# core_io2.net
KiCad netlist of a schematic drawn in EAGLE
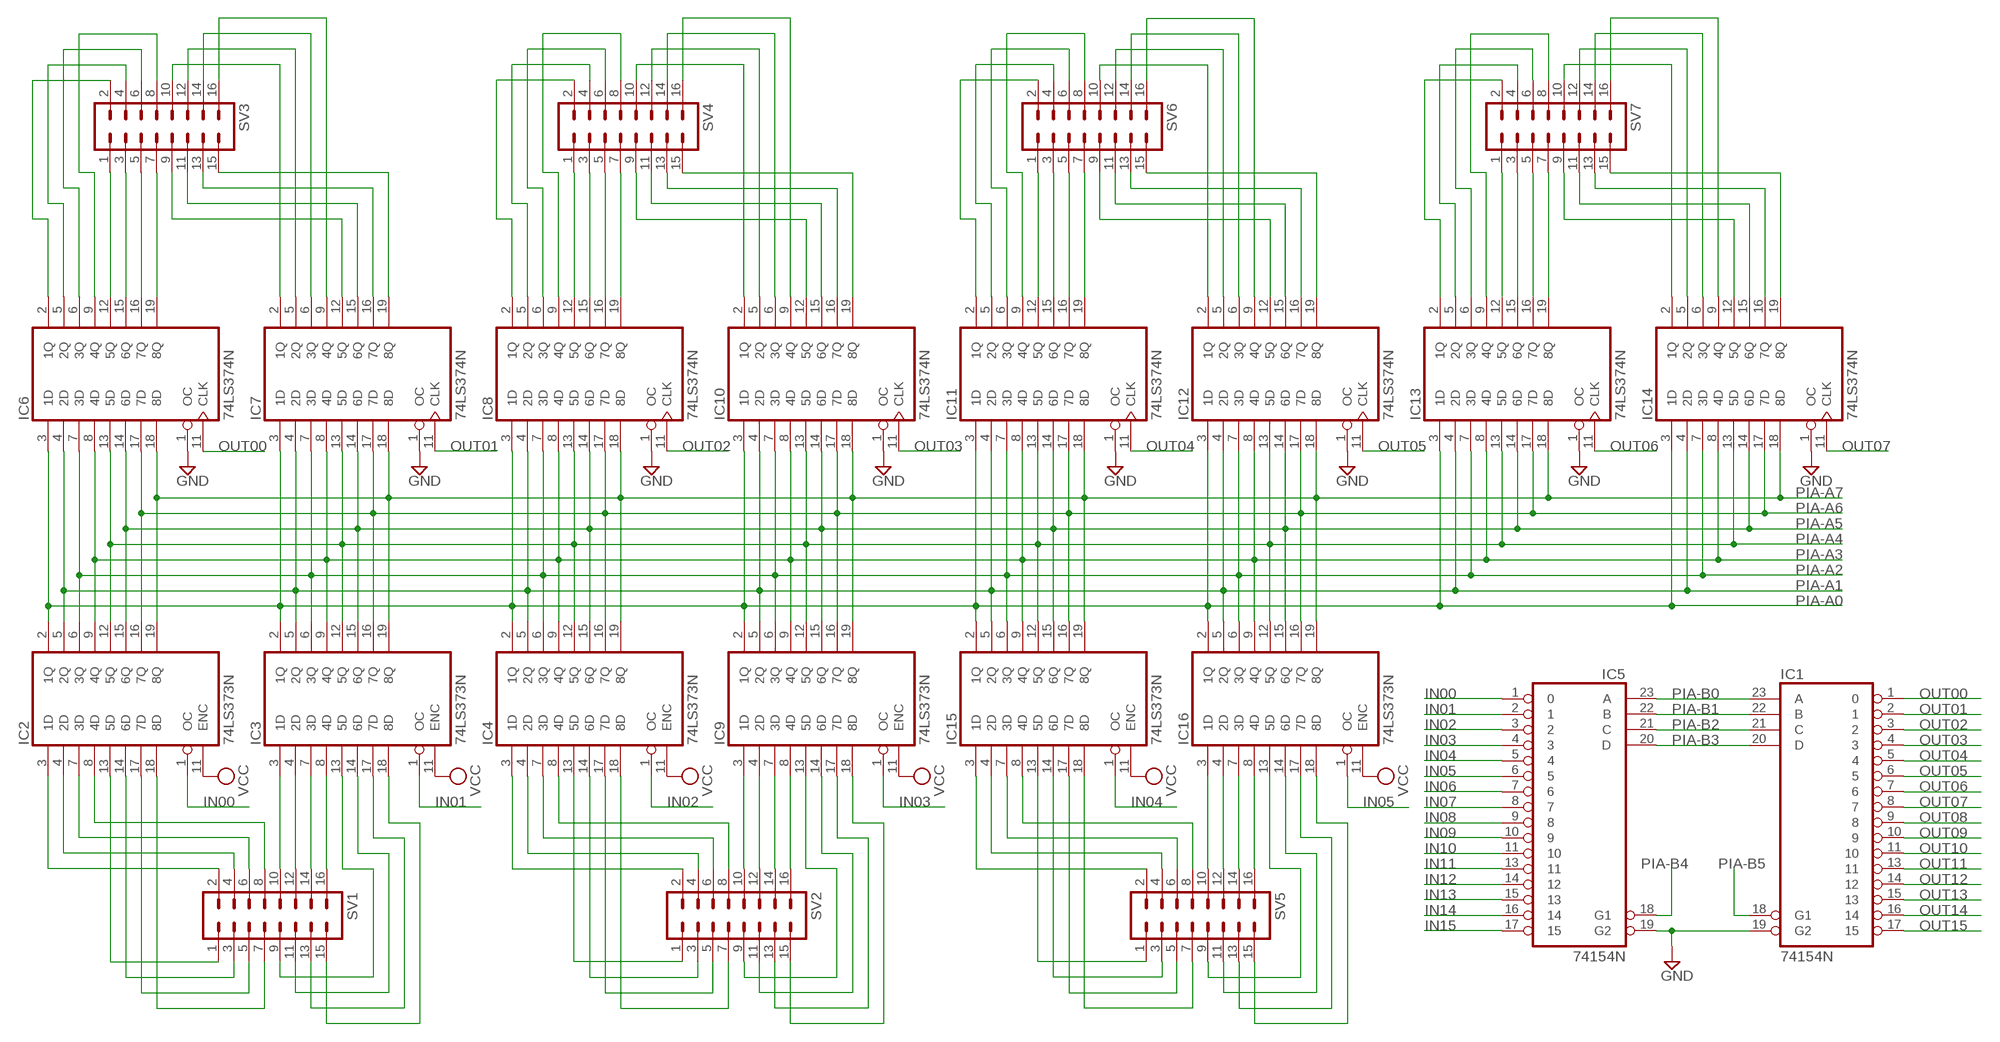
[diagram p0: schematic, sheet 1]
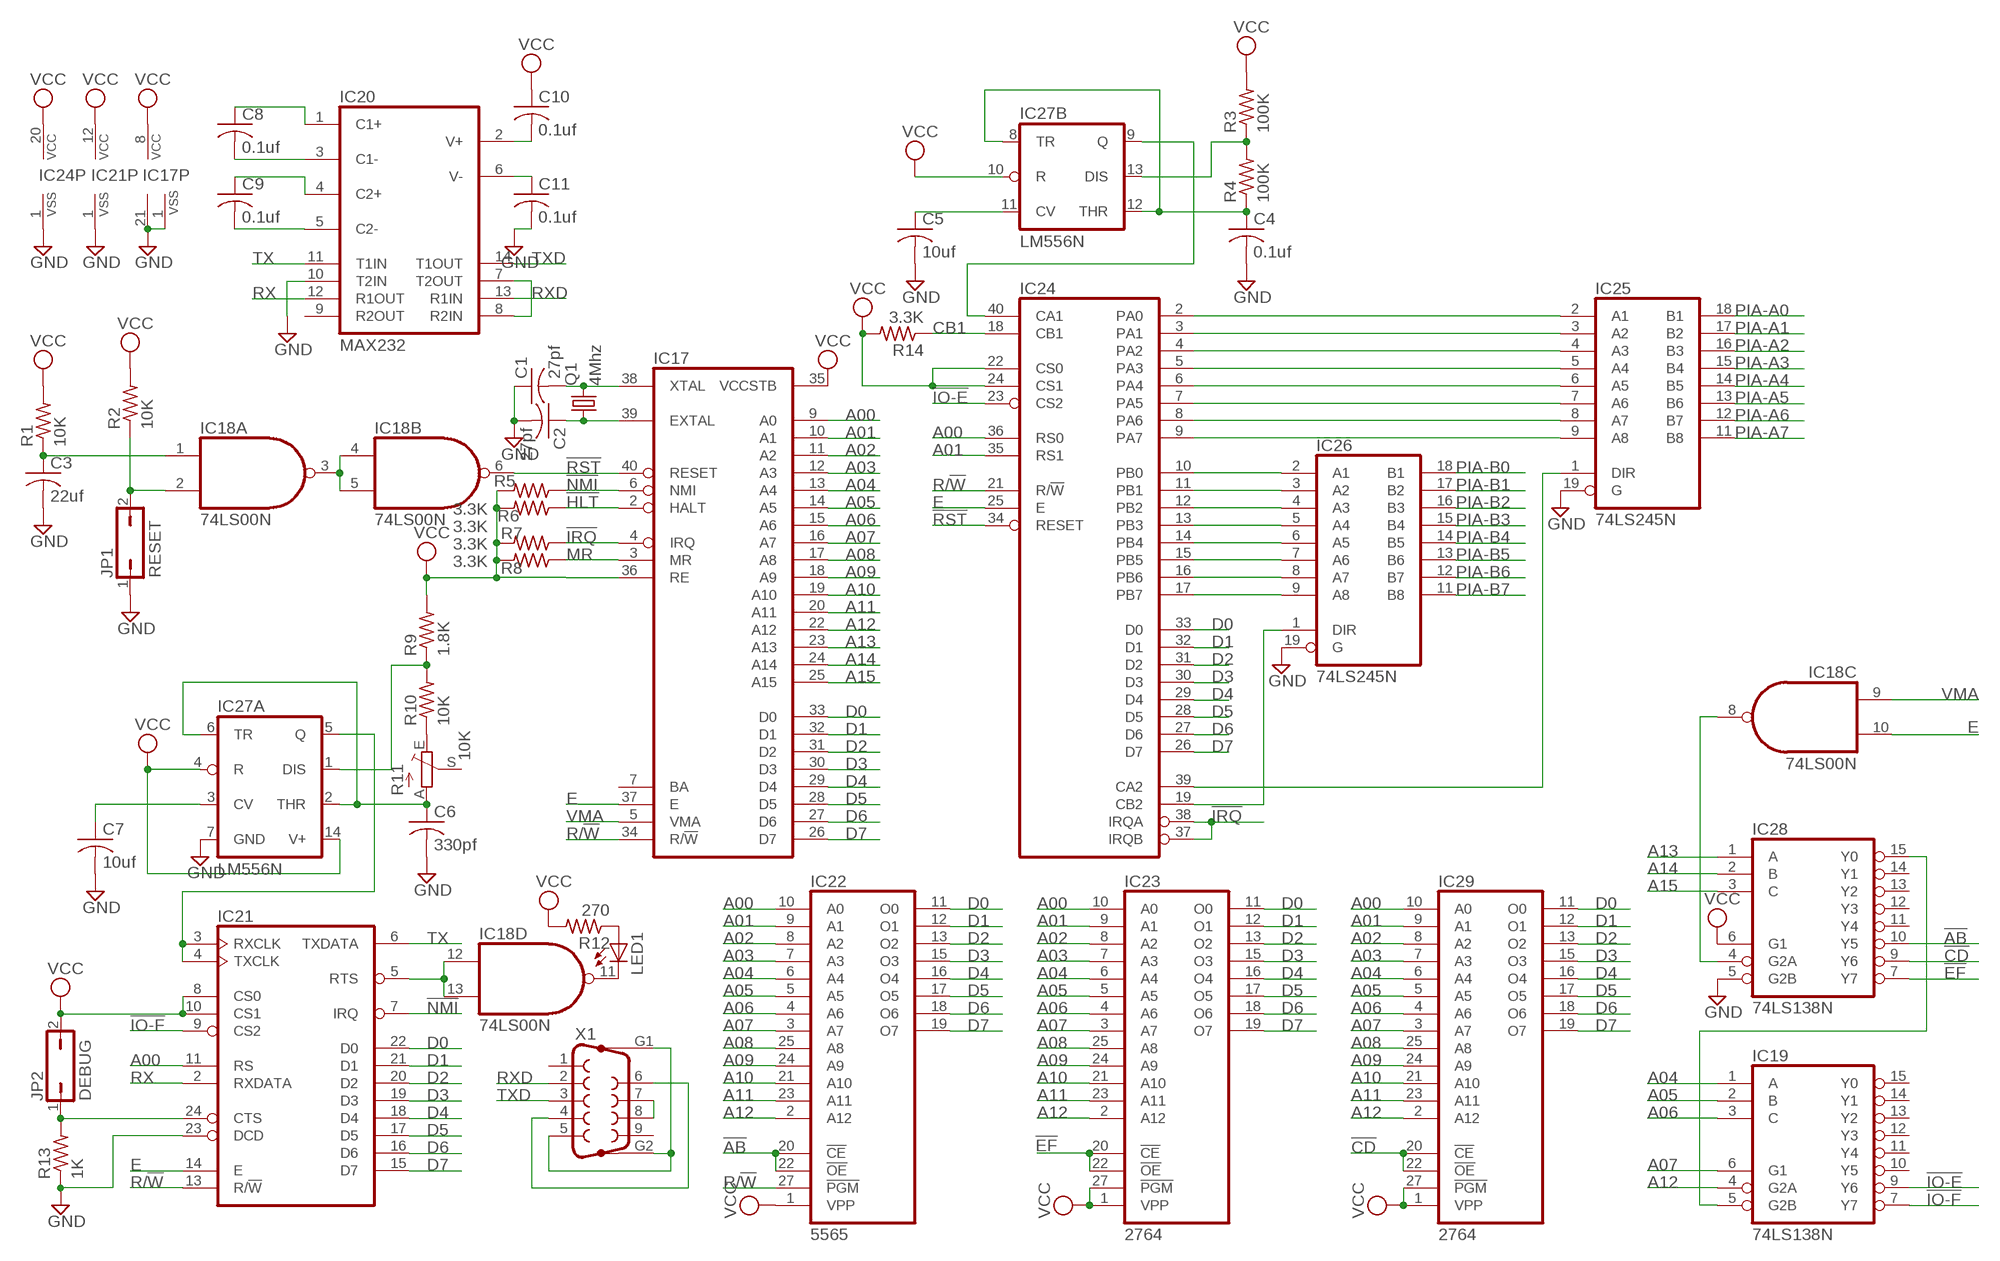
[diagram p1: schematic, sheet 2]
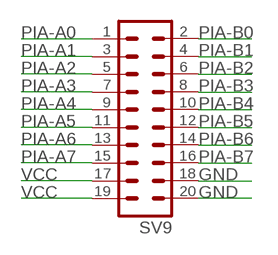
[diagram p2: schematic, sheet 3]

(export (version "E")
  (design (tool "Eeschema 10.0.6"))
  (components
    (comp (ref "SV9")
      (value "MA10-2")
      (footprint "eagle-import:MA10-2")
      (libsource (lib "eagle-import") (part "MA10-2"))
    )
    (comp (ref "IC1")
      (value "74154N")
      (footprint "eagle-import:DIL24-6")
      (libsource (lib "eagle-import") (part "74154N"))
    )
    (comp (ref "IC2")
      (value "74LS373N")
      (footprint "eagle-import:DIL20")
      (libsource (lib "eagle-import") (part "74373NLS"))
    )
    (comp (ref "IC3")
      (value "74LS373N")
      (footprint "eagle-import:DIL20")
      (libsource (lib "eagle-import") (part "74373NLS"))
    )
    (comp (ref "IC4")
      (value "74LS373N")
      (footprint "eagle-import:DIL20")
      (libsource (lib "eagle-import") (part "74373NLS"))
    )
    (comp (ref "IC5")
      (value "74154N")
      (footprint "eagle-import:DIL24-6")
      (libsource (lib "eagle-import") (part "74154N"))
    )
    (comp (ref "IC6")
      (value "74LS374N")
      (footprint "eagle-import:DIL20")
      (libsource (lib "eagle-import") (part "74374NLS"))
    )
    (comp (ref "IC7")
      (value "74LS374N")
      (footprint "eagle-import:DIL20")
      (libsource (lib "eagle-import") (part "74374NLS"))
    )
    (comp (ref "IC8")
      (value "74LS374N")
      (footprint "eagle-import:DIL20")
      (libsource (lib "eagle-import") (part "74374NLS"))
    )
    (comp (ref "IC9")
      (value "74LS373N")
      (footprint "eagle-import:DIL20")
      (libsource (lib "eagle-import") (part "74373NLS"))
    )
    (comp (ref "IC10")
      (value "74LS374N")
      (footprint "eagle-import:DIL20")
      (libsource (lib "eagle-import") (part "74374NLS"))
    )
    (comp (ref "IC11")
      (value "74LS374N")
      (footprint "eagle-import:DIL20")
      (libsource (lib "eagle-import") (part "74374NLS"))
    )
    (comp (ref "IC12")
      (value "74LS374N")
      (footprint "eagle-import:DIL20")
      (libsource (lib "eagle-import") (part "74374NLS"))
    )
    (comp (ref "IC13")
      (value "74LS374N")
      (footprint "eagle-import:DIL20")
      (libsource (lib "eagle-import") (part "74374NLS"))
    )
    (comp (ref "IC14")
      (value "74LS374N")
      (footprint "eagle-import:DIL20")
      (libsource (lib "eagle-import") (part "74374NLS"))
    )
    (comp (ref "IC15")
      (value "74LS373N")
      (footprint "eagle-import:DIL20")
      (libsource (lib "eagle-import") (part "74373NLS"))
    )
    (comp (ref "IC16")
      (value "74LS373N")
      (footprint "eagle-import:DIL20")
      (libsource (lib "eagle-import") (part "74373NLS"))
    )
    (comp (ref "SV1")
      (value "MA08-2")
      (footprint "eagle-import:MA08-2")
      (libsource (lib "eagle-import") (part "MA08-2"))
    )
    (comp (ref "SV2")
      (value "MA08-2")
      (footprint "eagle-import:MA08-2")
      (libsource (lib "eagle-import") (part "MA08-2"))
    )
    (comp (ref "SV3")
      (value "MA08-2")
      (footprint "eagle-import:MA08-2")
      (libsource (lib "eagle-import") (part "MA08-2"))
    )
    (comp (ref "SV4")
      (value "MA08-2")
      (footprint "eagle-import:MA08-2")
      (libsource (lib "eagle-import") (part "MA08-2"))
    )
    (comp (ref "SV5")
      (value "MA08-2")
      (footprint "eagle-import:MA08-2")
      (libsource (lib "eagle-import") (part "MA08-2"))
    )
    (comp (ref "SV6")
      (value "MA08-2")
      (footprint "eagle-import:MA08-2")
      (libsource (lib "eagle-import") (part "MA08-2"))
    )
    (comp (ref "SV7")
      (value "MA08-2")
      (footprint "eagle-import:MA08-2")
      (libsource (lib "eagle-import") (part "MA08-2"))
    )
    (comp (ref "C1")
      (value "27pf")
      (footprint "eagle-import:C050-025X075")
      (libsource (lib "eagle-import") (part "C-US050-025X075"))
    )
    (comp (ref "C2")
      (value "27pf")
      (footprint "eagle-import:C050-025X075")
      (libsource (lib "eagle-import") (part "C-US050-025X075"))
    )
    (comp (ref "C3")
      (value "22uf")
      (footprint "eagle-import:C050-025X075")
      (libsource (lib "eagle-import") (part "C-US050-025X075"))
    )
    (comp (ref "C4")
      (value "0.1uf")
      (footprint "eagle-import:C050-025X075")
      (libsource (lib "eagle-import") (part "C-US050-025X075"))
    )
    (comp (ref "C5")
      (value "10uf")
      (footprint "eagle-import:C050-025X075")
      (libsource (lib "eagle-import") (part "C-US050-025X075"))
    )
    (comp (ref "C6")
      (value "330pf")
      (footprint "eagle-import:C050-025X075")
      (libsource (lib "eagle-import") (part "C-US050-025X075"))
    )
    (comp (ref "C7")
      (value "10uf")
      (footprint "eagle-import:C050-025X075")
      (libsource (lib "eagle-import") (part "C-US050-025X075"))
    )
    (comp (ref "C8")
      (value "0.1uf")
      (footprint "eagle-import:C050-025X075")
      (libsource (lib "eagle-import") (part "C-US050-025X075"))
    )
    (comp (ref "C9")
      (value "0.1uf")
      (footprint "eagle-import:C050-025X075")
      (libsource (lib "eagle-import") (part "C-US050-025X075"))
    )
    (comp (ref "C10")
      (value "0.1uf")
      (footprint "eagle-import:C050-025X075")
      (libsource (lib "eagle-import") (part "C-US050-025X075"))
    )
    (comp (ref "C11")
      (value "0.1uf")
      (footprint "eagle-import:C050-025X075")
      (libsource (lib "eagle-import") (part "C-US050-025X075"))
    )
    (comp (ref "IC17")
      (value "6802")
      (footprint "eagle-import:DIL40")
      (libsource (lib "eagle-import") (part "6802"))
    )
    (comp (ref "IC18")
      (value "74LS00N")
      (footprint "eagle-import:DIL14")
      (libsource (lib "eagle-import") (part "7400NLS"))
    )
    (comp (ref "IC19")
      (value "74LS138N")
      (footprint "eagle-import:DIL16")
      (libsource (lib "eagle-import") (part "74138NLS"))
    )
    (comp (ref "IC20")
      (value "MAX232")
      (footprint "eagle-import:DIL16")
      (fields (field (name "MF") "MAXIM") (field (name "MPN") "MAX232ACPE+"))
      (libsource (lib "eagle-import") (part "MAX232"))
    )
    (comp (ref "IC21")
      (value "6850")
      (footprint "eagle-import:DIL24")
      (fields (field (name "MF") "NTE ELECTRONICS") (field (name "MPN") "NTE6850"))
      (libsource (lib "eagle-import") (part "6850"))
    )
    (comp (ref "IC22")
      (value "5565")
      (footprint "eagle-import:DIL28")
      (libsource (lib "eagle-import") (part "2764"))
    )
    (comp (ref "IC23")
      (value "2764")
      (footprint "eagle-import:DIL28")
      (libsource (lib "eagle-import") (part "2764"))
    )
    (comp (ref "IC24")
      (value "6821")
      (footprint "eagle-import:DIL40")
      (fields (field (name "MF") "NTE ELECTRONICS") (field (name "MPN") "NTE6821"))
      (libsource (lib "eagle-import") (part "6821"))
    )
    (comp (ref "IC25")
      (value "74LS245N")
      (footprint "eagle-import:DIL20")
      (libsource (lib "eagle-import") (part "74245NLS"))
    )
    (comp (ref "IC26")
      (value "74LS245N")
      (footprint "eagle-import:DIL20")
      (libsource (lib "eagle-import") (part "74245NLS"))
    )
    (comp (ref "IC27")
      (value "LM556N")
      (footprint "eagle-import:DIL14")
      (libsource (lib "eagle-import") (part "556NLM"))
    )
    (comp (ref "IC28")
      (value "74LS138N")
      (footprint "eagle-import:DIL16")
      (libsource (lib "eagle-import") (part "74138NLS"))
    )
    (comp (ref "IC29")
      (value "2764")
      (footprint "eagle-import:DIL28")
      (libsource (lib "eagle-import") (part "2764"))
    )
    (comp (ref "JP1")
      (value "RESET")
      (footprint "eagle-import:JP1")
      (libsource (lib "eagle-import") (part "JP1Q"))
    )
    (comp (ref "JP2")
      (value "DEBUG")
      (footprint "eagle-import:JP1")
      (libsource (lib "eagle-import") (part "JP1Q"))
    )
    (comp (ref "LED1")
      (value "LED3MM")
      (footprint "eagle-import:LED3MM")
      (libsource (lib "eagle-import") (part "LED3MM"))
    )
    (comp (ref "Q1")
      (value "4Mhz")
      (footprint "eagle-import:HC18U-V")
      (libsource (lib "eagle-import") (part "CRYSTALHC18U-V"))
    )
    (comp (ref "R1")
      (value "10K")
      (footprint "eagle-import:0207_7")
      (libsource (lib "eagle-import") (part "R-US_0207/7"))
    )
    (comp (ref "R2")
      (value "10K")
      (footprint "eagle-import:0207_7")
      (libsource (lib "eagle-import") (part "R-US_0207/7"))
    )
    (comp (ref "R3")
      (value "100K")
      (footprint "eagle-import:0207_7")
      (libsource (lib "eagle-import") (part "R-US_0207/7"))
    )
    (comp (ref "R4")
      (value "100K")
      (footprint "eagle-import:0207_7")
      (libsource (lib "eagle-import") (part "R-US_0207/7"))
    )
    (comp (ref "R5")
      (value "3.3K")
      (footprint "eagle-import:0207_7")
      (libsource (lib "eagle-import") (part "R-US_0207/7"))
    )
    (comp (ref "R6")
      (value "3.3K")
      (footprint "eagle-import:0207_7")
      (libsource (lib "eagle-import") (part "R-US_0207/7"))
    )
    (comp (ref "R7")
      (value "3.3K")
      (footprint "eagle-import:0207_7")
      (libsource (lib "eagle-import") (part "R-US_0207/7"))
    )
    (comp (ref "R8")
      (value "3.3K")
      (footprint "eagle-import:0207_7")
      (libsource (lib "eagle-import") (part "R-US_0207/7"))
    )
    (comp (ref "R9")
      (value "1.8K")
      (footprint "eagle-import:0207_7")
      (libsource (lib "eagle-import") (part "R-US_0207/7"))
    )
    (comp (ref "R10")
      (value "10K")
      (footprint "eagle-import:0207_7")
      (libsource (lib "eagle-import") (part "R-US_0207/7"))
    )
    (comp (ref "R11")
      (value "10K")
      (footprint "eagle-import:SP19L")
      (libsource (lib "eagle-import") (part "TRIM_EU-B90P"))
    )
    (comp (ref "R12")
      (value "270")
      (footprint "eagle-import:0207_7")
      (libsource (lib "eagle-import") (part "R-US_0207/7"))
    )
    (comp (ref "R13")
      (value "1K")
      (footprint "eagle-import:0207_7")
      (libsource (lib "eagle-import") (part "R-US_0207/7"))
    )
    (comp (ref "R14")
      (value "3.3K")
      (footprint "eagle-import:0207_7")
      (libsource (lib "eagle-import") (part "R-US_0207/7"))
    )
    (comp (ref "X1")
      (value "F09HP")
      (footprint "eagle-import:F09HP")
      (libsource (lib "eagle-import") (part "F09HP"))
    )
  )
  (nets
    (net (code "1") (name "A00") (class "Default")
      (node (ref "IC17") (pin "9") (pinfunction "A0_9") (pintype "output"))
      (node (ref "IC21") (pin "11") (pinfunction "RS_11") (pintype "input"))
      (node (ref "IC22") (pin "10") (pinfunction "A0_10") (pintype "input"))
      (node (ref "IC23") (pin "10") (pinfunction "A0_10") (pintype "input"))
      (node (ref "IC24") (pin "36") (pinfunction "RS0_36") (pintype "input"))
      (node (ref "IC29") (pin "10") (pinfunction "A0_10") (pintype "input"))
    )
    (net (code "2") (name "A01") (class "Default")
      (node (ref "IC17") (pin "10") (pinfunction "A1_10") (pintype "output"))
      (node (ref "IC22") (pin "9") (pinfunction "A1_9") (pintype "input"))
      (node (ref "IC23") (pin "9") (pinfunction "A1_9") (pintype "input"))
      (node (ref "IC24") (pin "35") (pinfunction "RS1_35") (pintype "input"))
      (node (ref "IC29") (pin "9") (pinfunction "A1_9") (pintype "input"))
    )
    (net (code "3") (name "A02") (class "Default")
      (node (ref "IC17") (pin "11") (pinfunction "A2_11") (pintype "output"))
      (node (ref "IC22") (pin "8") (pinfunction "A2_8") (pintype "input"))
      (node (ref "IC23") (pin "8") (pinfunction "A2_8") (pintype "input"))
      (node (ref "IC29") (pin "8") (pinfunction "A2_8") (pintype "input"))
    )
    (net (code "4") (name "A03") (class "Default")
      (node (ref "IC17") (pin "12") (pinfunction "A3_12") (pintype "output"))
      (node (ref "IC22") (pin "7") (pinfunction "A3_7") (pintype "input"))
      (node (ref "IC23") (pin "7") (pinfunction "A3_7") (pintype "input"))
      (node (ref "IC29") (pin "7") (pinfunction "A3_7") (pintype "input"))
    )
    (net (code "5") (name "A04") (class "Default")
      (node (ref "IC17") (pin "13") (pinfunction "A4_13") (pintype "output"))
      (node (ref "IC19") (pin "1") (pinfunction "A_1") (pintype "input"))
      (node (ref "IC22") (pin "6") (pinfunction "A4_6") (pintype "input"))
      (node (ref "IC23") (pin "6") (pinfunction "A4_6") (pintype "input"))
      (node (ref "IC29") (pin "6") (pinfunction "A4_6") (pintype "input"))
    )
    (net (code "6") (name "A05") (class "Default")
      (node (ref "IC17") (pin "14") (pinfunction "A5_14") (pintype "output"))
      (node (ref "IC19") (pin "2") (pinfunction "B_2") (pintype "input"))
      (node (ref "IC22") (pin "5") (pinfunction "A5_5") (pintype "input"))
      (node (ref "IC23") (pin "5") (pinfunction "A5_5") (pintype "input"))
      (node (ref "IC29") (pin "5") (pinfunction "A5_5") (pintype "input"))
    )
    (net (code "7") (name "A06") (class "Default")
      (node (ref "IC17") (pin "15") (pinfunction "A6_15") (pintype "output"))
      (node (ref "IC19") (pin "3") (pinfunction "C_3") (pintype "input"))
      (node (ref "IC22") (pin "4") (pinfunction "A6_4") (pintype "input"))
      (node (ref "IC23") (pin "4") (pinfunction "A6_4") (pintype "input"))
      (node (ref "IC29") (pin "4") (pinfunction "A6_4") (pintype "input"))
    )
    (net (code "8") (name "A07") (class "Default")
      (node (ref "IC17") (pin "16") (pinfunction "A7_16") (pintype "output"))
      (node (ref "IC19") (pin "6") (pinfunction "G1_6") (pintype "input"))
      (node (ref "IC22") (pin "3") (pinfunction "A7_3") (pintype "input"))
      (node (ref "IC23") (pin "3") (pinfunction "A7_3") (pintype "input"))
      (node (ref "IC29") (pin "3") (pinfunction "A7_3") (pintype "input"))
    )
    (net (code "9") (name "A08") (class "Default")
      (node (ref "IC17") (pin "17") (pinfunction "A8_17") (pintype "output"))
      (node (ref "IC22") (pin "25") (pinfunction "A8_25") (pintype "input"))
      (node (ref "IC23") (pin "25") (pinfunction "A8_25") (pintype "input"))
      (node (ref "IC29") (pin "25") (pinfunction "A8_25") (pintype "input"))
    )
    (net (code "10") (name "A09") (class "Default")
      (node (ref "IC17") (pin "18") (pinfunction "A9_18") (pintype "output"))
      (node (ref "IC22") (pin "24") (pinfunction "A9_24") (pintype "input"))
      (node (ref "IC23") (pin "24") (pinfunction "A9_24") (pintype "input"))
      (node (ref "IC29") (pin "24") (pinfunction "A9_24") (pintype "input"))
    )
    (net (code "11") (name "A10") (class "Default")
      (node (ref "IC17") (pin "19") (pinfunction "A10_19") (pintype "output"))
      (node (ref "IC22") (pin "21") (pinfunction "A10_21") (pintype "input"))
      (node (ref "IC23") (pin "21") (pinfunction "A10_21") (pintype "input"))
      (node (ref "IC29") (pin "21") (pinfunction "A10_21") (pintype "input"))
    )
    (net (code "12") (name "A11") (class "Default")
      (node (ref "IC17") (pin "20") (pinfunction "A11_20") (pintype "output"))
      (node (ref "IC22") (pin "23") (pinfunction "A11_23") (pintype "input"))
      (node (ref "IC23") (pin "23") (pinfunction "A11_23") (pintype "input"))
      (node (ref "IC29") (pin "23") (pinfunction "A11_23") (pintype "input"))
    )
    (net (code "13") (name "A12") (class "Default")
      (node (ref "IC17") (pin "22") (pinfunction "A12_22") (pintype "output"))
      (node (ref "IC19") (pin "4") (pinfunction "G2A_4") (pintype "input"))
      (node (ref "IC22") (pin "2") (pinfunction "A12_2") (pintype "input"))
      (node (ref "IC23") (pin "2") (pinfunction "A12_2") (pintype "input"))
      (node (ref "IC29") (pin "2") (pinfunction "A12_2") (pintype "input"))
    )
    (net (code "14") (name "A13") (class "Default")
      (node (ref "IC17") (pin "23") (pinfunction "A13_23") (pintype "output"))
      (node (ref "IC28") (pin "1") (pinfunction "A_1") (pintype "input"))
    )
    (net (code "15") (name "A14") (class "Default")
      (node (ref "IC17") (pin "24") (pinfunction "A14_24") (pintype "output"))
      (node (ref "IC28") (pin "2") (pinfunction "B_2") (pintype "input"))
    )
    (net (code "16") (name "A15") (class "Default")
      (node (ref "IC17") (pin "25") (pinfunction "A15_25") (pintype "output"))
      (node (ref "IC28") (pin "3") (pinfunction "C_3") (pintype "input"))
    )
    (net (code "17") (name "CB1") (class "Default")
      (node (ref "IC24") (pin "18") (pinfunction "CB1_18") (pintype "input"))
      (node (ref "R14") (pin "1") (pinfunction "1_1") (pintype "passive"))
    )
    (net (code "18") (name "D0") (class "Default")
      (node (ref "IC17") (pin "33") (pinfunction "D0_33") (pintype "bidirectional"))
      (node (ref "IC21") (pin "22") (pinfunction "D0_22") (pintype "bidirectional"))
      (node (ref "IC22") (pin "11") (pinfunction "O0_11") (pintype "tri_state"))
      (node (ref "IC23") (pin "11") (pinfunction "O0_11") (pintype "tri_state"))
      (node (ref "IC24") (pin "33") (pinfunction "D0_33") (pintype "bidirectional"))
      (node (ref "IC29") (pin "11") (pinfunction "O0_11") (pintype "tri_state"))
    )
    (net (code "19") (name "D1") (class "Default")
      (node (ref "IC17") (pin "32") (pinfunction "D1_32") (pintype "bidirectional"))
      (node (ref "IC21") (pin "21") (pinfunction "D1_21") (pintype "bidirectional"))
      (node (ref "IC22") (pin "12") (pinfunction "O1_12") (pintype "tri_state"))
      (node (ref "IC23") (pin "12") (pinfunction "O1_12") (pintype "tri_state"))
      (node (ref "IC24") (pin "32") (pinfunction "D1_32") (pintype "bidirectional"))
      (node (ref "IC29") (pin "12") (pinfunction "O1_12") (pintype "tri_state"))
    )
    (net (code "20") (name "D2") (class "Default")
      (node (ref "IC17") (pin "31") (pinfunction "D2_31") (pintype "bidirectional"))
      (node (ref "IC21") (pin "20") (pinfunction "D2_20") (pintype "bidirectional"))
      (node (ref "IC22") (pin "13") (pinfunction "O2_13") (pintype "tri_state"))
      (node (ref "IC23") (pin "13") (pinfunction "O2_13") (pintype "tri_state"))
      (node (ref "IC24") (pin "31") (pinfunction "D2_31") (pintype "bidirectional"))
      (node (ref "IC29") (pin "13") (pinfunction "O2_13") (pintype "tri_state"))
    )
    (net (code "21") (name "D3") (class "Default")
      (node (ref "IC17") (pin "30") (pinfunction "D3_30") (pintype "bidirectional"))
      (node (ref "IC21") (pin "19") (pinfunction "D3_19") (pintype "bidirectional"))
      (node (ref "IC22") (pin "15") (pinfunction "O3_15") (pintype "tri_state"))
      (node (ref "IC23") (pin "15") (pinfunction "O3_15") (pintype "tri_state"))
      (node (ref "IC24") (pin "30") (pinfunction "D3_30") (pintype "bidirectional"))
      (node (ref "IC29") (pin "15") (pinfunction "O3_15") (pintype "tri_state"))
    )
    (net (code "22") (name "D4") (class "Default")
      (node (ref "IC17") (pin "29") (pinfunction "D4_29") (pintype "bidirectional"))
      (node (ref "IC21") (pin "18") (pinfunction "D4_18") (pintype "bidirectional"))
      (node (ref "IC22") (pin "16") (pinfunction "O4_16") (pintype "tri_state"))
      (node (ref "IC23") (pin "16") (pinfunction "O4_16") (pintype "tri_state"))
      (node (ref "IC24") (pin "29") (pinfunction "D4_29") (pintype "bidirectional"))
      (node (ref "IC29") (pin "16") (pinfunction "O4_16") (pintype "tri_state"))
    )
    (net (code "23") (name "D5") (class "Default")
      (node (ref "IC17") (pin "28") (pinfunction "D5_28") (pintype "bidirectional"))
      (node (ref "IC21") (pin "17") (pinfunction "D5_17") (pintype "bidirectional"))
      (node (ref "IC22") (pin "17") (pinfunction "O5_17") (pintype "tri_state"))
      (node (ref "IC23") (pin "17") (pinfunction "O5_17") (pintype "tri_state"))
      (node (ref "IC24") (pin "28") (pinfunction "D5_28") (pintype "bidirectional"))
      (node (ref "IC29") (pin "17") (pinfunction "O5_17") (pintype "tri_state"))
    )
    (net (code "24") (name "D6") (class "Default")
      (node (ref "IC17") (pin "27") (pinfunction "D6_27") (pintype "bidirectional"))
      (node (ref "IC21") (pin "16") (pinfunction "D6_16") (pintype "bidirectional"))
      (node (ref "IC22") (pin "18") (pinfunction "O6_18") (pintype "tri_state"))
      (node (ref "IC23") (pin "18") (pinfunction "O6_18") (pintype "tri_state"))
      (node (ref "IC24") (pin "27") (pinfunction "D6_27") (pintype "bidirectional"))
      (node (ref "IC29") (pin "18") (pinfunction "O6_18") (pintype "tri_state"))
    )
    (net (code "25") (name "D7") (class "Default")
      (node (ref "IC17") (pin "26") (pinfunction "D7_26") (pintype "bidirectional"))
      (node (ref "IC21") (pin "15") (pinfunction "D7_15") (pintype "bidirectional"))
      (node (ref "IC22") (pin "19") (pinfunction "O7_19") (pintype "tri_state"))
      (node (ref "IC23") (pin "19") (pinfunction "O7_19") (pintype "tri_state"))
      (node (ref "IC24") (pin "26") (pinfunction "D7_26") (pintype "bidirectional"))
      (node (ref "IC29") (pin "19") (pinfunction "O7_19") (pintype "tri_state"))
    )
    (net (code "26") (name "E") (class "Default")
      (node (ref "IC17") (pin "37") (pinfunction "E_37") (pintype "output"))
      (node (ref "IC18") (pin "10") (pinfunction "I1_10") (pintype "input"))
      (node (ref "IC21") (pin "14") (pinfunction "E_14") (pintype "input"))
      (node (ref "IC24") (pin "25") (pinfunction "E_25") (pintype "input"))
    )
    (net (code "27") (name "GND") (class "Default")
      (node (ref "C1") (pin "1") (pinfunction "1_1") (pintype "passive"))
      (node (ref "C11") (pin "2") (pinfunction "2_2") (pintype "passive"))
      (node (ref "C2") (pin "2") (pinfunction "2_2") (pintype "passive"))
      (node (ref "C3") (pin "2") (pinfunction "2_2") (pintype "passive"))
      (node (ref "C4") (pin "2") (pinfunction "2_2") (pintype "passive"))
      (node (ref "C5") (pin "2") (pinfunction "2_2") (pintype "passive"))
      (node (ref "C6") (pin "2") (pinfunction "2_2") (pintype "passive"))
      (node (ref "C7") (pin "2") (pinfunction "2_2") (pintype "passive"))
      (node (ref "IC1") (pin "19") (pinfunction "G2_19") (pintype "input"))
      (node (ref "IC10") (pin "1") (pinfunction "OC_1") (pintype "input"))
      (node (ref "IC11") (pin "1") (pinfunction "OC_1") (pintype "input"))
      (node (ref "IC12") (pin "1") (pinfunction "OC_1") (pintype "input"))
      (node (ref "IC13") (pin "1") (pinfunction "OC_1") (pintype "input"))
      (node (ref "IC14") (pin "1") (pinfunction "OC_1") (pintype "input"))
      (node (ref "IC17") (pin "1") (pinfunction "VSS_1") (pintype "power_in"))
      (node (ref "IC17") (pin "21") (pinfunction "VSS_21") (pintype "power_in"))
      (node (ref "IC20") (pin "10") (pinfunction "T2IN_10") (pintype "input"))
      (node (ref "IC21") (pin "1") (pinfunction "VSS_1") (pintype "power_in"))
      (node (ref "IC21") (pin "23") (pinfunction "DCD_23") (pintype "input"))
      (node (ref "IC24") (pin "1") (pinfunction "VSS_1") (pintype "power_in"))
      (node (ref "IC25") (pin "19") (pinfunction "G_19") (pintype "input"))
      (node (ref "IC26") (pin "19") (pinfunction "G_19") (pintype "input"))
      (node (ref "IC27") (pin "7") (pinfunction "GND_7") (pintype "power_in"))
      (node (ref "IC28") (pin "5") (pinfunction "G2B_5") (pintype "input"))
      (node (ref "IC5") (pin "19") (pinfunction "G2_19") (pintype "input"))
      (node (ref "IC6") (pin "1") (pinfunction "OC_1") (pintype "input"))
      (node (ref "IC7") (pin "1") (pinfunction "OC_1") (pintype "input"))
      (node (ref "IC8") (pin "1") (pinfunction "OC_1") (pintype "input"))
      (node (ref "JP1") (pin "1") (pinfunction "1_1") (pintype "passive"))
      (node (ref "R13") (pin "1") (pinfunction "1_1") (pintype "passive"))
      (node (ref "SV9") (pin "18") (pinfunction "18_18") (pintype "passive"))
      (node (ref "SV9") (pin "20") (pinfunction "20_20") (pintype "passive"))
    )
    (net (code "28") (name "IN00") (class "Default")
      (node (ref "IC2") (pin "1") (pinfunction "OC_1") (pintype "input"))
      (node (ref "IC5") (pin "1") (pinfunction "0_1") (pintype "output"))
    )
    (net (code "29") (name "IN01") (class "Default")
      (node (ref "IC3") (pin "1") (pinfunction "OC_1") (pintype "input"))
      (node (ref "IC5") (pin "2") (pinfunction "1_2") (pintype "output"))
    )
    (net (code "30") (name "IN02") (class "Default")
      (node (ref "IC4") (pin "1") (pinfunction "OC_1") (pintype "input"))
      (node (ref "IC5") (pin "3") (pinfunction "2_3") (pintype "output"))
    )
    (net (code "31") (name "IN03") (class "Default")
      (node (ref "IC5") (pin "4") (pinfunction "3_4") (pintype "output"))
      (node (ref "IC9") (pin "1") (pinfunction "OC_1") (pintype "input"))
    )
    (net (code "32") (name "IN04") (class "Default")
      (node (ref "IC15") (pin "1") (pinfunction "OC_1") (pintype "input"))
      (node (ref "IC5") (pin "5") (pinfunction "4_5") (pintype "output"))
    )
    (net (code "33") (name "IN05") (class "Default")
      (node (ref "IC16") (pin "1") (pinfunction "OC_1") (pintype "input"))
      (node (ref "IC5") (pin "6") (pinfunction "5_6") (pintype "output"))
    )
    (net (code "34") (name "IN06") (class "Default")
      (node (ref "IC5") (pin "7") (pinfunction "6_7") (pintype "output"))
    )
    (net (code "35") (name "IN07") (class "Default")
      (node (ref "IC5") (pin "8") (pinfunction "7_8") (pintype "output"))
    )
    (net (code "36") (name "IN08") (class "Default")
      (node (ref "IC5") (pin "9") (pinfunction "8_9") (pintype "output"))
    )
    (net (code "37") (name "IN09") (class "Default")
      (node (ref "IC5") (pin "10") (pinfunction "9_10") (pintype "output"))
    )
    (net (code "38") (name "IN10") (class "Default")
      (node (ref "IC5") (pin "11") (pinfunction "10_11") (pintype "output"))
    )
    (net (code "39") (name "IN11") (class "Default")
      (node (ref "IC5") (pin "13") (pinfunction "11_13") (pintype "output"))
    )
    (net (code "40") (name "IN12") (class "Default")
      (node (ref "IC5") (pin "14") (pinfunction "12_14") (pintype "output"))
    )
    (net (code "41") (name "IN13") (class "Default")
      (node (ref "IC5") (pin "15") (pinfunction "13_15") (pintype "output"))
    )
    (net (code "42") (name "IN14") (class "Default")
      (node (ref "IC5") (pin "16") (pinfunction "14_16") (pintype "output"))
    )
    (net (code "43") (name "IN15") (class "Default")
      (node (ref "IC5") (pin "17") (pinfunction "15_17") (pintype "output"))
    )
    (net (code "44") (name "MR") (class "Default")
      (node (ref "IC17") (pin "3") (pinfunction "MR_3") (pintype "input"))
      (node (ref "R8") (pin "1") (pinfunction "1_1") (pintype "passive"))
    )
    (net (code "45") (name "Net-(IC2A-1D)") (class "Default")
      (node (ref "IC2") (pin "3") (pinfunction "1D_3") (pintype "input"))
      (node (ref "SV1") (pin "2") (pinfunction "2_2") (pintype "passive"))
    )
    (net (code "46") (name "Net-(IC2A-2D)") (class "Default")
      (node (ref "IC2") (pin "4") (pinfunction "2D_4") (pintype "input"))
      (node (ref "SV1") (pin "4") (pinfunction "4_4") (pintype "passive"))
    )
    (net (code "47") (name "Net-(IC2A-3D)") (class "Default")
      (node (ref "IC2") (pin "7") (pinfunction "3D_7") (pintype "input"))
      (node (ref "SV1") (pin "6") (pinfunction "6_6") (pintype "passive"))
    )
    (net (code "48") (name "Net-(IC2A-4D)") (class "Default")
      (node (ref "IC2") (pin "8") (pinfunction "4D_8") (pintype "input"))
      (node (ref "SV1") (pin "8") (pinfunction "8_8") (pintype "passive"))
    )
    (net (code "49") (name "Net-(IC2A-5D)") (class "Default")
      (node (ref "IC2") (pin "13") (pinfunction "5D_13") (pintype "input"))
      (node (ref "SV1") (pin "1") (pinfunction "1_1") (pintype "passive"))
    )
    (net (code "50") (name "Net-(IC2A-6D)") (class "Default")
      (node (ref "IC2") (pin "14") (pinfunction "6D_14") (pintype "input"))
      (node (ref "SV1") (pin "3") (pinfunction "3_3") (pintype "passive"))
    )
    (net (code "51") (name "Net-(IC2A-7D)") (class "Default")
      (node (ref "IC2") (pin "17") (pinfunction "7D_17") (pintype "input"))
      (node (ref "SV1") (pin "5") (pinfunction "5_5") (pintype "passive"))
    )
    (net (code "52") (name "Net-(IC2A-8D)") (class "Default")
      (node (ref "IC2") (pin "18") (pinfunction "8D_18") (pintype "input"))
      (node (ref "SV1") (pin "7") (pinfunction "7_7") (pintype "passive"))
    )
    (net (code "53") (name "Net-(IC3A-1D)") (class "Default")
      (node (ref "IC3") (pin "3") (pinfunction "1D_3") (pintype "input"))
      (node (ref "SV1") (pin "10") (pinfunction "10_10") (pintype "passive"))
    )
    (net (code "54") (name "Net-(IC3A-2D)") (class "Default")
      (node (ref "IC3") (pin "4") (pinfunction "2D_4") (pintype "input"))
      (node (ref "SV1") (pin "12") (pinfunction "12_12") (pintype "passive"))
    )
    (net (code "55") (name "Net-(IC3A-3D)") (class "Default")
      (node (ref "IC3") (pin "7") (pinfunction "3D_7") (pintype "input"))
      (node (ref "SV1") (pin "14") (pinfunction "14_14") (pintype "passive"))
    )
    (net (code "56") (name "Net-(IC3A-4D)") (class "Default")
      (node (ref "IC3") (pin "8") (pinfunction "4D_8") (pintype "input"))
      (node (ref "SV1") (pin "16") (pinfunction "16_16") (pintype "passive"))
    )
    (net (code "57") (name "Net-(IC3A-5D)") (class "Default")
      (node (ref "IC3") (pin "13") (pinfunction "5D_13") (pintype "input"))
      (node (ref "SV1") (pin "9") (pinfunction "9_9") (pintype "passive"))
    )
    (net (code "58") (name "Net-(IC3A-6D)") (class "Default")
      (node (ref "IC3") (pin "14") (pinfunction "6D_14") (pintype "input"))
      (node (ref "SV1") (pin "11") (pinfunction "11_11") (pintype "passive"))
    )
    (net (code "59") (name "Net-(IC3A-7D)") (class "Default")
      (node (ref "IC3") (pin "17") (pinfunction "7D_17") (pintype "input"))
      (node (ref "SV1") (pin "13") (pinfunction "13_13") (pintype "passive"))
    )
    (net (code "60") (name "Net-(IC3A-8D)") (class "Default")
      (node (ref "IC3") (pin "18") (pinfunction "8D_18") (pintype "input"))
      (node (ref "SV1") (pin "15") (pinfunction "15_15") (pintype "passive"))
    )
    (net (code "61") (name "Net-(IC4A-1D)") (class "Default")
      (node (ref "IC4") (pin "3") (pinfunction "1D_3") (pintype "input"))
      (node (ref "SV2") (pin "2") (pinfunction "2_2") (pintype "passive"))
    )
    (net (code "62") (name "Net-(IC4A-2D)") (class "Default")
      (node (ref "IC4") (pin "4") (pinfunction "2D_4") (pintype "input"))
      (node (ref "SV2") (pin "4") (pinfunction "4_4") (pintype "passive"))
    )
    (net (code "63") (name "Net-(IC4A-3D)") (class "Default")
      (node (ref "IC4") (pin "7") (pinfunction "3D_7") (pintype "input"))
      (node (ref "SV2") (pin "6") (pinfunction "6_6") (pintype "passive"))
    )
    (net (code "64") (name "Net-(IC4A-4D)") (class "Default")
      (node (ref "IC4") (pin "8") (pinfunction "4D_8") (pintype "input"))
      (node (ref "SV2") (pin "8") (pinfunction "8_8") (pintype "passive"))
    )
    (net (code "65") (name "Net-(IC4A-5D)") (class "Default")
      (node (ref "IC4") (pin "13") (pinfunction "5D_13") (pintype "input"))
      (node (ref "SV2") (pin "1") (pinfunction "1_1") (pintype "passive"))
    )
    (net (code "66") (name "Net-(IC4A-6D)") (class "Default")
      (node (ref "IC4") (pin "14") (pinfunction "6D_14") (pintype "input"))
      (node (ref "SV2") (pin "3") (pinfunction "3_3") (pintype "passive"))
    )
    (net (code "67") (name "Net-(IC4A-7D)") (class "Default")
      (node (ref "IC4") (pin "17") (pinfunction "7D_17") (pintype "input"))
      (node (ref "SV2") (pin "5") (pinfunction "5_5") (pintype "passive"))
    )
    (net (code "68") (name "Net-(IC4A-8D)") (class "Default")
      (node (ref "IC4") (pin "18") (pinfunction "8D_18") (pintype "input"))
      (node (ref "SV2") (pin "7") (pinfunction "7_7") (pintype "passive"))
    )
    (net (code "69") (name "Net-(IC6A-1Q)") (class "Default")
      (node (ref "IC6") (pin "2") (pinfunction "1Q_2") (pintype "tri_state"))
      (node (ref "SV3") (pin "2") (pinfunction "2_2") (pintype "passive"))
    )
    (net (code "70") (name "Net-(IC6A-2Q)") (class "Default")
      (node (ref "IC6") (pin "5") (pinfunction "2Q_5") (pintype "tri_state"))
      (node (ref "SV3") (pin "4") (pinfunction "4_4") (pintype "passive"))
    )
    (net (code "71") (name "Net-(IC6A-3Q)") (class "Default")
      (node (ref "IC6") (pin "6") (pinfunction "3Q_6") (pintype "tri_state"))
      (node (ref "SV3") (pin "6") (pinfunction "6_6") (pintype "passive"))
    )
    (net (code "72") (name "Net-(IC6A-4Q)") (class "Default")
      (node (ref "IC6") (pin "9") (pinfunction "4Q_9") (pintype "tri_state"))
      (node (ref "SV3") (pin "8") (pinfunction "8_8") (pintype "passive"))
    )
    (net (code "73") (name "Net-(IC6A-5Q)") (class "Default")
      (node (ref "IC6") (pin "12") (pinfunction "5Q_12") (pintype "tri_state"))
      (node (ref "SV3") (pin "1") (pinfunction "1_1") (pintype "passive"))
    )
    (net (code "74") (name "Net-(IC6A-6Q)") (class "Default")
      (node (ref "IC6") (pin "15") (pinfunction "6Q_15") (pintype "tri_state"))
      (node (ref "SV3") (pin "3") (pinfunction "3_3") (pintype "passive"))
    )
    (net (code "75") (name "Net-(IC6A-7Q)") (class "Default")
      (node (ref "IC6") (pin "16") (pinfunction "7Q_16") (pintype "tri_state"))
      (node (ref "SV3") (pin "5") (pinfunction "5_5") (pintype "passive"))
    )
    (net (code "76") (name "Net-(IC6A-8Q)") (class "Default")
      (node (ref "IC6") (pin "19") (pinfunction "8Q_19") (pintype "tri_state"))
      (node (ref "SV3") (pin "7") (pinfunction "7_7") (pintype "passive"))
    )
    (net (code "77") (name "Net-(IC7A-1Q)") (class "Default")
      (node (ref "IC7") (pin "2") (pinfunction "1Q_2") (pintype "tri_state"))
      (node (ref "SV3") (pin "10") (pinfunction "10_10") (pintype "passive"))
    )
    (net (code "78") (name "Net-(IC7A-2Q)") (class "Default")
      (node (ref "IC7") (pin "5") (pinfunction "2Q_5") (pintype "tri_state"))
      (node (ref "SV3") (pin "12") (pinfunction "12_12") (pintype "passive"))
    )
    (net (code "79") (name "Net-(IC7A-3Q)") (class "Default")
      (node (ref "IC7") (pin "6") (pinfunction "3Q_6") (pintype "tri_state"))
      (node (ref "SV3") (pin "14") (pinfunction "14_14") (pintype "passive"))
    )
    (net (code "80") (name "Net-(IC7A-4Q)") (class "Default")
      (node (ref "IC7") (pin "9") (pinfunction "4Q_9") (pintype "tri_state"))
      (node (ref "SV3") (pin "16") (pinfunction "16_16") (pintype "passive"))
    )
    (net (code "81") (name "Net-(IC7A-5Q)") (class "Default")
      (node (ref "IC7") (pin "12") (pinfunction "5Q_12") (pintype "tri_state"))
      (node (ref "SV3") (pin "9") (pinfunction "9_9") (pintype "passive"))
    )
    (net (code "82") (name "Net-(IC7A-6Q)") (class "Default")
      (node (ref "IC7") (pin "15") (pinfunction "6Q_15") (pintype "tri_state"))
      (node (ref "SV3") (pin "11") (pinfunction "11_11") (pintype "passive"))
    )
    (net (code "83") (name "Net-(IC7A-7Q)") (class "Default")
      (node (ref "IC7") (pin "16") (pinfunction "7Q_16") (pintype "tri_state"))
      (node (ref "SV3") (pin "13") (pinfunction "13_13") (pintype "passive"))
    )
    (net (code "84") (name "Net-(IC7A-8Q)") (class "Default")
      (node (ref "IC7") (pin "19") (pinfunction "8Q_19") (pintype "tri_state"))
      (node (ref "SV3") (pin "15") (pinfunction "15_15") (pintype "passive"))
    )
    (net (code "85") (name "Net-(IC8A-1Q)") (class "Default")
      (node (ref "IC8") (pin "2") (pinfunction "1Q_2") (pintype "tri_state"))
      (node (ref "SV4") (pin "2") (pinfunction "2_2") (pintype "passive"))
    )
    (net (code "86") (name "Net-(IC8A-2Q)") (class "Default")
      (node (ref "IC8") (pin "5") (pinfunction "2Q_5") (pintype "tri_state"))
      (node (ref "SV4") (pin "4") (pinfunction "4_4") (pintype "passive"))
    )
    (net (code "87") (name "Net-(IC8A-3Q)") (class "Default")
      (node (ref "IC8") (pin "6") (pinfunction "3Q_6") (pintype "tri_state"))
      (node (ref "SV4") (pin "6") (pinfunction "6_6") (pintype "passive"))
    )
    (net (code "88") (name "Net-(IC8A-4Q)") (class "Default")
      (node (ref "IC8") (pin "9") (pinfunction "4Q_9") (pintype "tri_state"))
      (node (ref "SV4") (pin "8") (pinfunction "8_8") (pintype "passive"))
    )
    (net (code "89") (name "Net-(IC8A-5Q)") (class "Default")
      (node (ref "IC8") (pin "12") (pinfunction "5Q_12") (pintype "tri_state"))
      (node (ref "SV4") (pin "1") (pinfunction "1_1") (pintype "passive"))
    )
    (net (code "90") (name "Net-(IC8A-6Q)") (class "Default")
      (node (ref "IC8") (pin "15") (pinfunction "6Q_15") (pintype "tri_state"))
      (node (ref "SV4") (pin "3") (pinfunction "3_3") (pintype "passive"))
    )
    (net (code "91") (name "Net-(IC8A-7Q)") (class "Default")
      (node (ref "IC8") (pin "16") (pinfunction "7Q_16") (pintype "tri_state"))
      (node (ref "SV4") (pin "5") (pinfunction "5_5") (pintype "passive"))
    )
    (net (code "92") (name "Net-(IC8A-8Q)") (class "Default")
      (node (ref "IC8") (pin "19") (pinfunction "8Q_19") (pintype "tri_state"))
      (node (ref "SV4") (pin "7") (pinfunction "7_7") (pintype "passive"))
    )
    (net (code "93") (name "Net-(IC9A-1D)") (class "Default")
      (node (ref "IC9") (pin "3") (pinfunction "1D_3") (pintype "input"))
      (node (ref "SV2") (pin "10") (pinfunction "10_10") (pintype "passive"))
    )
    (net (code "94") (name "Net-(IC9A-2D)") (class "Default")
      (node (ref "IC9") (pin "4") (pinfunction "2D_4") (pintype "input"))
      (node (ref "SV2") (pin "12") (pinfunction "12_12") (pintype "passive"))
    )
    (net (code "95") (name "Net-(IC9A-3D)") (class "Default")
      (node (ref "IC9") (pin "7") (pinfunction "3D_7") (pintype "input"))
      (node (ref "SV2") (pin "14") (pinfunction "14_14") (pintype "passive"))
    )
    (net (code "96") (name "Net-(IC9A-4D)") (class "Default")
      (node (ref "IC9") (pin "8") (pinfunction "4D_8") (pintype "input"))
      (node (ref "SV2") (pin "16") (pinfunction "16_16") (pintype "passive"))
    )
    (net (code "97") (name "Net-(IC9A-5D)") (class "Default")
      (node (ref "IC9") (pin "13") (pinfunction "5D_13") (pintype "input"))
      (node (ref "SV2") (pin "9") (pinfunction "9_9") (pintype "passive"))
    )
    (net (code "98") (name "Net-(IC9A-6D)") (class "Default")
      (node (ref "IC9") (pin "14") (pinfunction "6D_14") (pintype "input"))
      (node (ref "SV2") (pin "11") (pinfunction "11_11") (pintype "passive"))
    )
    (net (code "99") (name "Net-(IC9A-7D)") (class "Default")
      (node (ref "IC9") (pin "17") (pinfunction "7D_17") (pintype "input"))
      (node (ref "SV2") (pin "13") (pinfunction "13_13") (pintype "passive"))
    )
    (net (code "100") (name "Net-(IC9A-8D)") (class "Default")
      (node (ref "IC9") (pin "18") (pinfunction "8D_18") (pintype "input"))
      (node (ref "SV2") (pin "15") (pinfunction "15_15") (pintype "passive"))
    )
    (net (code "101") (name "Net-(IC10A-1Q)") (class "Default")
      (node (ref "IC10") (pin "2") (pinfunction "1Q_2") (pintype "tri_state"))
      (node (ref "SV4") (pin "10") (pinfunction "10_10") (pintype "passive"))
    )
    (net (code "102") (name "Net-(IC10A-2Q)") (class "Default")
      (node (ref "IC10") (pin "5") (pinfunction "2Q_5") (pintype "tri_state"))
      (node (ref "SV4") (pin "12") (pinfunction "12_12") (pintype "passive"))
    )
    (net (code "103") (name "Net-(IC10A-3Q)") (class "Default")
      (node (ref "IC10") (pin "6") (pinfunction "3Q_6") (pintype "tri_state"))
      (node (ref "SV4") (pin "14") (pinfunction "14_14") (pintype "passive"))
    )
    (net (code "104") (name "Net-(IC10A-4Q)") (class "Default")
      (node (ref "IC10") (pin "9") (pinfunction "4Q_9") (pintype "tri_state"))
      (node (ref "SV4") (pin "16") (pinfunction "16_16") (pintype "passive"))
    )
    (net (code "105") (name "Net-(IC10A-5Q)") (class "Default")
      (node (ref "IC10") (pin "12") (pinfunction "5Q_12") (pintype "tri_state"))
      (node (ref "SV4") (pin "9") (pinfunction "9_9") (pintype "passive"))
    )
    (net (code "106") (name "Net-(IC10A-6Q)") (class "Default")
      (node (ref "IC10") (pin "15") (pinfunction "6Q_15") (pintype "tri_state"))
      (node (ref "SV4") (pin "11") (pinfunction "11_11") (pintype "passive"))
    )
    (net (code "107") (name "Net-(IC10A-7Q)") (class "Default")
      (node (ref "IC10") (pin "16") (pinfunction "7Q_16") (pintype "tri_state"))
      (node (ref "SV4") (pin "13") (pinfunction "13_13") (pintype "passive"))
    )
    (net (code "108") (name "Net-(IC10A-8Q)") (class "Default")
      (node (ref "IC10") (pin "19") (pinfunction "8Q_19") (pintype "tri_state"))
      (node (ref "SV4") (pin "15") (pinfunction "15_15") (pintype "passive"))
    )
    (net (code "109") (name "Net-(IC11A-1Q)") (class "Default")
      (node (ref "IC11") (pin "2") (pinfunction "1Q_2") (pintype "tri_state"))
      (node (ref "SV6") (pin "2") (pinfunction "2_2") (pintype "passive"))
    )
    (net (code "110") (name "Net-(IC11A-2Q)") (class "Default")
      (node (ref "IC11") (pin "5") (pinfunction "2Q_5") (pintype "tri_state"))
      (node (ref "SV6") (pin "4") (pinfunction "4_4") (pintype "passive"))
    )
    (net (code "111") (name "Net-(IC11A-3Q)") (class "Default")
      (node (ref "IC11") (pin "6") (pinfunction "3Q_6") (pintype "tri_state"))
      (node (ref "SV6") (pin "6") (pinfunction "6_6") (pintype "passive"))
    )
    (net (code "112") (name "Net-(IC11A-4Q)") (class "Default")
      (node (ref "IC11") (pin "9") (pinfunction "4Q_9") (pintype "tri_state"))
      (node (ref "SV6") (pin "8") (pinfunction "8_8") (pintype "passive"))
    )
    (net (code "113") (name "Net-(IC11A-5Q)") (class "Default")
      (node (ref "IC11") (pin "12") (pinfunction "5Q_12") (pintype "tri_state"))
      (node (ref "SV6") (pin "1") (pinfunction "1_1") (pintype "passive"))
    )
    (net (code "114") (name "Net-(IC11A-6Q)") (class "Default")
      (node (ref "IC11") (pin "15") (pinfunction "6Q_15") (pintype "tri_state"))
      (node (ref "SV6") (pin "3") (pinfunction "3_3") (pintype "passive"))
    )
    (net (code "115") (name "Net-(IC11A-7Q)") (class "Default")
      (node (ref "IC11") (pin "16") (pinfunction "7Q_16") (pintype "tri_state"))
      (node (ref "SV6") (pin "5") (pinfunction "5_5") (pintype "passive"))
    )
    (net (code "116") (name "Net-(IC11A-8Q)") (class "Default")
      (node (ref "IC11") (pin "19") (pinfunction "8Q_19") (pintype "tri_state"))
      (node (ref "SV6") (pin "7") (pinfunction "7_7") (pintype "passive"))
    )
    (net (code "117") (name "Net-(IC12A-1Q)") (class "Default")
      (node (ref "IC12") (pin "2") (pinfunction "1Q_2") (pintype "tri_state"))
      (node (ref "SV6") (pin "10") (pinfunction "10_10") (pintype "passive"))
    )
    (net (code "118") (name "Net-(IC12A-2Q)") (class "Default")
      (node (ref "IC12") (pin "5") (pinfunction "2Q_5") (pintype "tri_state"))
      (node (ref "SV6") (pin "12") (pinfunction "12_12") (pintype "passive"))
    )
    (net (code "119") (name "Net-(IC12A-3Q)") (class "Default")
      (node (ref "IC12") (pin "6") (pinfunction "3Q_6") (pintype "tri_state"))
      (node (ref "SV6") (pin "14") (pinfunction "14_14") (pintype "passive"))
    )
    (net (code "120") (name "Net-(IC12A-4Q)") (class "Default")
      (node (ref "IC12") (pin "9") (pinfunction "4Q_9") (pintype "tri_state"))
      (node (ref "SV6") (pin "16") (pinfunction "16_16") (pintype "passive"))
    )
    (net (code "121") (name "Net-(IC12A-5Q)") (class "Default")
      (node (ref "IC12") (pin "12") (pinfunction "5Q_12") (pintype "tri_state"))
      (node (ref "SV6") (pin "9") (pinfunction "9_9") (pintype "passive"))
    )
    (net (code "122") (name "Net-(IC12A-6Q)") (class "Default")
      (node (ref "IC12") (pin "15") (pinfunction "6Q_15") (pintype "tri_state"))
      (node (ref "SV6") (pin "11") (pinfunction "11_11") (pintype "passive"))
    )
    (net (code "123") (name "Net-(IC12A-7Q)") (class "Default")
      (node (ref "IC12") (pin "16") (pinfunction "7Q_16") (pintype "tri_state"))
      (node (ref "SV6") (pin "13") (pinfunction "13_13") (pintype "passive"))
    )
    (net (code "124") (name "Net-(IC12A-8Q)") (class "Default")
      (node (ref "IC12") (pin "19") (pinfunction "8Q_19") (pintype "tri_state"))
      (node (ref "SV6") (pin "15") (pinfunction "15_15") (pintype "passive"))
    )
    (net (code "125") (name "Net-(IC13A-1Q)") (class "Default")
      (node (ref "IC13") (pin "2") (pinfunction "1Q_2") (pintype "tri_state"))
      (node (ref "SV7") (pin "2") (pinfunction "2_2") (pintype "passive"))
    )
    (net (code "126") (name "Net-(IC13A-2Q)") (class "Default")
      (node (ref "IC13") (pin "5") (pinfunction "2Q_5") (pintype "tri_state"))
      (node (ref "SV7") (pin "4") (pinfunction "4_4") (pintype "passive"))
    )
    (net (code "127") (name "Net-(IC13A-3Q)") (class "Default")
      (node (ref "IC13") (pin "6") (pinfunction "3Q_6") (pintype "tri_state"))
      (node (ref "SV7") (pin "6") (pinfunction "6_6") (pintype "passive"))
    )
    (net (code "128") (name "Net-(IC13A-4Q)") (class "Default")
      (node (ref "IC13") (pin "9") (pinfunction "4Q_9") (pintype "tri_state"))
      (node (ref "SV7") (pin "8") (pinfunction "8_8") (pintype "passive"))
    )
    (net (code "129") (name "Net-(IC13A-5Q)") (class "Default")
      (node (ref "IC13") (pin "12") (pinfunction "5Q_12") (pintype "tri_state"))
      (node (ref "SV7") (pin "1") (pinfunction "1_1") (pintype "passive"))
    )
    (net (code "130") (name "Net-(IC13A-6Q)") (class "Default")
      (node (ref "IC13") (pin "15") (pinfunction "6Q_15") (pintype "tri_state"))
      (node (ref "SV7") (pin "3") (pinfunction "3_3") (pintype "passive"))
    )
    (net (code "131") (name "Net-(IC13A-7Q)") (class "Default")
      (node (ref "IC13") (pin "16") (pinfunction "7Q_16") (pintype "tri_state"))
      (node (ref "SV7") (pin "5") (pinfunction "5_5") (pintype "passive"))
    )
    (net (code "132") (name "Net-(IC13A-8Q)") (class "Default")
      (node (ref "IC13") (pin "19") (pinfunction "8Q_19") (pintype "tri_state"))
      (node (ref "SV7") (pin "7") (pinfunction "7_7") (pintype "passive"))
    )
    (net (code "133") (name "Net-(IC14A-1Q)") (class "Default")
      (node (ref "IC14") (pin "2") (pinfunction "1Q_2") (pintype "tri_state"))
      (node (ref "SV7") (pin "10") (pinfunction "10_10") (pintype "passive"))
    )
    (net (code "134") (name "Net-(IC14A-2Q)") (class "Default")
      (node (ref "IC14") (pin "5") (pinfunction "2Q_5") (pintype "tri_state"))
      (node (ref "SV7") (pin "12") (pinfunction "12_12") (pintype "passive"))
    )
    (net (code "135") (name "Net-(IC14A-3Q)") (class "Default")
      (node (ref "IC14") (pin "6") (pinfunction "3Q_6") (pintype "tri_state"))
      (node (ref "SV7") (pin "14") (pinfunction "14_14") (pintype "passive"))
    )
    (net (code "136") (name "Net-(IC14A-4Q)") (class "Default")
      (node (ref "IC14") (pin "9") (pinfunction "4Q_9") (pintype "tri_state"))
      (node (ref "SV7") (pin "16") (pinfunction "16_16") (pintype "passive"))
    )
    (net (code "137") (name "Net-(IC14A-5Q)") (class "Default")
      (node (ref "IC14") (pin "12") (pinfunction "5Q_12") (pintype "tri_state"))
      (node (ref "SV7") (pin "9") (pinfunction "9_9") (pintype "passive"))
    )
    (net (code "138") (name "Net-(IC14A-6Q)") (class "Default")
      (node (ref "IC14") (pin "15") (pinfunction "6Q_15") (pintype "tri_state"))
      (node (ref "SV7") (pin "11") (pinfunction "11_11") (pintype "passive"))
    )
    (net (code "139") (name "Net-(IC14A-7Q)") (class "Default")
      (node (ref "IC14") (pin "16") (pinfunction "7Q_16") (pintype "tri_state"))
      (node (ref "SV7") (pin "13") (pinfunction "13_13") (pintype "passive"))
    )
    (net (code "140") (name "Net-(IC14A-8Q)") (class "Default")
      (node (ref "IC14") (pin "19") (pinfunction "8Q_19") (pintype "tri_state"))
      (node (ref "SV7") (pin "15") (pinfunction "15_15") (pintype "passive"))
    )
    (net (code "141") (name "Net-(IC15A-1D)") (class "Default")
      (node (ref "IC15") (pin "3") (pinfunction "1D_3") (pintype "input"))
      (node (ref "SV5") (pin "2") (pinfunction "2_2") (pintype "passive"))
    )
    (net (code "142") (name "Net-(IC15A-2D)") (class "Default")
      (node (ref "IC15") (pin "4") (pinfunction "2D_4") (pintype "input"))
      (node (ref "SV5") (pin "4") (pinfunction "4_4") (pintype "passive"))
    )
    (net (code "143") (name "Net-(IC15A-3D)") (class "Default")
      (node (ref "IC15") (pin "7") (pinfunction "3D_7") (pintype "input"))
      (node (ref "SV5") (pin "6") (pinfunction "6_6") (pintype "passive"))
    )
    (net (code "144") (name "Net-(IC15A-4D)") (class "Default")
      (node (ref "IC15") (pin "8") (pinfunction "4D_8") (pintype "input"))
      (node (ref "SV5") (pin "8") (pinfunction "8_8") (pintype "passive"))
    )
    (net (code "145") (name "Net-(IC15A-5D)") (class "Default")
      (node (ref "IC15") (pin "13") (pinfunction "5D_13") (pintype "input"))
      (node (ref "SV5") (pin "1") (pinfunction "1_1") (pintype "passive"))
    )
    (net (code "146") (name "Net-(IC15A-6D)") (class "Default")
      (node (ref "IC15") (pin "14") (pinfunction "6D_14") (pintype "input"))
      (node (ref "SV5") (pin "3") (pinfunction "3_3") (pintype "passive"))
    )
    (net (code "147") (name "Net-(IC15A-7D)") (class "Default")
      (node (ref "IC15") (pin "17") (pinfunction "7D_17") (pintype "input"))
      (node (ref "SV5") (pin "5") (pinfunction "5_5") (pintype "passive"))
    )
    (net (code "148") (name "Net-(IC15A-8D)") (class "Default")
      (node (ref "IC15") (pin "18") (pinfunction "8D_18") (pintype "input"))
      (node (ref "SV5") (pin "7") (pinfunction "7_7") (pintype "passive"))
    )
    (net (code "149") (name "Net-(IC16A-1D)") (class "Default")
      (node (ref "IC16") (pin "3") (pinfunction "1D_3") (pintype "input"))
      (node (ref "SV5") (pin "10") (pinfunction "10_10") (pintype "passive"))
    )
    (net (code "150") (name "Net-(IC16A-2D)") (class "Default")
      (node (ref "IC16") (pin "4") (pinfunction "2D_4") (pintype "input"))
      (node (ref "SV5") (pin "12") (pinfunction "12_12") (pintype "passive"))
    )
    (net (code "151") (name "Net-(IC16A-3D)") (class "Default")
      (node (ref "IC16") (pin "7") (pinfunction "3D_7") (pintype "input"))
      (node (ref "SV5") (pin "14") (pinfunction "14_14") (pintype "passive"))
    )
    (net (code "152") (name "Net-(IC16A-4D)") (class "Default")
      (node (ref "IC16") (pin "8") (pinfunction "4D_8") (pintype "input"))
      (node (ref "SV5") (pin "16") (pinfunction "16_16") (pintype "passive"))
    )
    (net (code "153") (name "Net-(IC16A-5D)") (class "Default")
      (node (ref "IC16") (pin "13") (pinfunction "5D_13") (pintype "input"))
      (node (ref "SV5") (pin "9") (pinfunction "9_9") (pintype "passive"))
    )
    (net (code "154") (name "Net-(IC16A-6D)") (class "Default")
      (node (ref "IC16") (pin "14") (pinfunction "6D_14") (pintype "input"))
      (node (ref "SV5") (pin "11") (pinfunction "11_11") (pintype "passive"))
    )
    (net (code "155") (name "Net-(IC16A-7D)") (class "Default")
      (node (ref "IC16") (pin "17") (pinfunction "7D_17") (pintype "input"))
      (node (ref "SV5") (pin "13") (pinfunction "13_13") (pintype "passive"))
    )
    (net (code "156") (name "Net-(IC16A-8D)") (class "Default")
      (node (ref "IC16") (pin "18") (pinfunction "8D_18") (pintype "input"))
      (node (ref "SV5") (pin "15") (pinfunction "15_15") (pintype "passive"))
    )
    (net (code "157") (name "Net-(IC17A-EXTAL)") (class "Default")
      (node (ref "C2") (pin "1") (pinfunction "1_1") (pintype "passive"))
      (node (ref "IC17") (pin "39") (pinfunction "EXTAL_39") (pintype "input"))
      (node (ref "Q1") (pin "1") (pinfunction "1_1") (pintype "passive"))
    )
    (net (code "158") (name "Net-(IC17A-XTAL)") (class "Default")
      (node (ref "C1") (pin "2") (pinfunction "2_2") (pintype "passive"))
      (node (ref "IC17") (pin "38") (pinfunction "XTAL_38") (pintype "input"))
      (node (ref "Q1") (pin "2") (pinfunction "2_2") (pintype "passive"))
    )
    (net (code "159") (name "Net-(IC18A-I0)") (class "Default")
      (node (ref "C3") (pin "1") (pinfunction "1_1") (pintype "passive"))
      (node (ref "IC18") (pin "1") (pinfunction "I0_1") (pintype "input"))
      (node (ref "R1") (pin "1") (pinfunction "1_1") (pintype "passive"))
    )
    (net (code "160") (name "Net-(IC18A-I1)") (class "Default")
      (node (ref "IC18") (pin "2") (pinfunction "I1_2") (pintype "input"))
      (node (ref "JP1") (pin "2") (pinfunction "2_2") (pintype "passive"))
      (node (ref "R2") (pin "1") (pinfunction "1_1") (pintype "passive"))
    )
    (net (code "161") (name "Net-(IC18A-O)") (class "Default")
      (node (ref "IC18") (pin "3") (pinfunction "O_3") (pintype "output"))
      (node (ref "IC18") (pin "4") (pinfunction "I0_4") (pintype "input"))
      (node (ref "IC18") (pin "5") (pinfunction "I1_5") (pintype "input"))
    )
    (net (code "162") (name "Net-(IC18C-O)") (class "Default")
      (node (ref "IC18") (pin "8") (pinfunction "O_8") (pintype "output"))
      (node (ref "IC28") (pin "4") (pinfunction "G2A_4") (pintype "input"))
    )
    (net (code "163") (name "Net-(IC18D-I0)") (class "Default")
      (node (ref "IC18") (pin "12") (pinfunction "I0_12") (pintype "input"))
      (node (ref "IC18") (pin "13") (pinfunction "I1_13") (pintype "input"))
      (node (ref "IC21") (pin "5") (pinfunction "RTS_5") (pintype "output"))
    )
    (net (code "164") (name "Net-(IC18D-O)") (class "Default")
      (node (ref "IC18") (pin "11") (pinfunction "O_11") (pintype "output"))
      (node (ref "LED1") (pin "K") (pinfunction "C_K") (pintype "passive"))
    )
    (net (code "165") (name "Net-(IC19A-G2B)") (class "Default")
      (node (ref "IC19") (pin "5") (pinfunction "G2B_5") (pintype "input"))
      (node (ref "IC28") (pin "15") (pinfunction "Y0_15") (pintype "output"))
    )
    (net (code "166") (name "Net-(IC20A-C1+)") (class "Default")
      (node (ref "C8") (pin "1") (pinfunction "1_1") (pintype "passive"))
      (node (ref "IC20") (pin "1") (pinfunction "C1+_1") (pintype "bidirectional"))
    )
    (net (code "167") (name "Net-(IC20A-C1-)") (class "Default")
      (node (ref "C8") (pin "2") (pinfunction "2_2") (pintype "passive"))
      (node (ref "IC20") (pin "3") (pinfunction "C1-_3") (pintype "bidirectional"))
    )
    (net (code "168") (name "Net-(IC20A-C2+)") (class "Default")
      (node (ref "C9") (pin "1") (pinfunction "1_1") (pintype "passive"))
      (node (ref "IC20") (pin "4") (pinfunction "C2+_4") (pintype "bidirectional"))
    )
    (net (code "169") (name "Net-(IC20A-C2-)") (class "Default")
      (node (ref "C9") (pin "2") (pinfunction "2_2") (pintype "passive"))
      (node (ref "IC20") (pin "5") (pinfunction "C2-_5") (pintype "bidirectional"))
    )
    (net (code "170") (name "Net-(IC20A-R2IN)") (class "Default")
      (node (ref "IC20") (pin "7") (pinfunction "T2OUT_7") (pintype "output"))
      (node (ref "IC20") (pin "8") (pinfunction "R2IN_8") (pintype "input"))
    )
    (net (code "171") (name "Net-(IC20A-V+)") (class "Default")
      (node (ref "C10") (pin "2") (pinfunction "2_2") (pintype "passive"))
      (node (ref "IC20") (pin "2") (pinfunction "V+_2") (pintype "bidirectional"))
    )
    (net (code "172") (name "Net-(IC20A-V-)") (class "Default")
      (node (ref "C11") (pin "1") (pinfunction "1_1") (pintype "passive"))
      (node (ref "IC20") (pin "6") (pinfunction "V-_6") (pintype "bidirectional"))
    )
    (net (code "173") (name "Net-(IC21A-CTS)") (class "Default")
      (node (ref "IC21") (pin "24") (pinfunction "CTS_24") (pintype "input"))
      (node (ref "JP2") (pin "1") (pinfunction "1_1") (pintype "passive"))
      (node (ref "R13") (pin "2") (pinfunction "2_2") (pintype "passive"))
    )
    (net (code "174") (name "Net-(IC21A-RXCLK)") (class "Default")
      (node (ref "IC21") (pin "3") (pinfunction "RXCLK_3") (pintype "input"))
      (node (ref "IC21") (pin "4") (pinfunction "TXCLK_4") (pintype "input"))
      (node (ref "IC27") (pin "5") (pinfunction "Q_5") (pintype "output"))
    )
    (net (code "175") (name "Net-(IC24A-CA1)") (class "Default")
      (node (ref "IC24") (pin "40") (pinfunction "CA1_40") (pintype "input"))
      (node (ref "IC27") (pin "9") (pinfunction "Q_9") (pintype "output"))
    )
    (net (code "176") (name "Net-(IC24A-CA2)") (class "Default")
      (node (ref "IC24") (pin "39") (pinfunction "CA2_39") (pintype "bidirectional"))
      (node (ref "IC25") (pin "1") (pinfunction "DIR_1") (pintype "input"))
    )
    (net (code "177") (name "Net-(IC24A-CB2)") (class "Default")
      (node (ref "IC24") (pin "19") (pinfunction "CB2_19") (pintype "bidirectional"))
      (node (ref "IC26") (pin "1") (pinfunction "DIR_1") (pintype "input"))
    )
    (net (code "178") (name "Net-(IC24A-PA0)") (class "Default")
      (node (ref "IC24") (pin "2") (pinfunction "PA0_2") (pintype "bidirectional"))
      (node (ref "IC25") (pin "2") (pinfunction "A1_2") (pintype "bidirectional"))
    )
    (net (code "179") (name "Net-(IC24A-PA1)") (class "Default")
      (node (ref "IC24") (pin "3") (pinfunction "PA1_3") (pintype "bidirectional"))
      (node (ref "IC25") (pin "3") (pinfunction "A2_3") (pintype "bidirectional"))
    )
    (net (code "180") (name "Net-(IC24A-PA2)") (class "Default")
      (node (ref "IC24") (pin "4") (pinfunction "PA2_4") (pintype "bidirectional"))
      (node (ref "IC25") (pin "4") (pinfunction "A3_4") (pintype "bidirectional"))
    )
    (net (code "181") (name "Net-(IC24A-PA3)") (class "Default")
      (node (ref "IC24") (pin "5") (pinfunction "PA3_5") (pintype "bidirectional"))
      (node (ref "IC25") (pin "5") (pinfunction "A4_5") (pintype "bidirectional"))
    )
    (net (code "182") (name "Net-(IC24A-PA4)") (class "Default")
      (node (ref "IC24") (pin "6") (pinfunction "PA4_6") (pintype "bidirectional"))
      (node (ref "IC25") (pin "6") (pinfunction "A5_6") (pintype "bidirectional"))
    )
    (net (code "183") (name "Net-(IC24A-PA5)") (class "Default")
      (node (ref "IC24") (pin "7") (pinfunction "PA5_7") (pintype "bidirectional"))
      (node (ref "IC25") (pin "7") (pinfunction "A6_7") (pintype "bidirectional"))
    )
    (net (code "184") (name "Net-(IC24A-PA6)") (class "Default")
      (node (ref "IC24") (pin "8") (pinfunction "PA6_8") (pintype "bidirectional"))
      (node (ref "IC25") (pin "8") (pinfunction "A7_8") (pintype "bidirectional"))
    )
    (net (code "185") (name "Net-(IC24A-PA7)") (class "Default")
      (node (ref "IC24") (pin "9") (pinfunction "PA7_9") (pintype "bidirectional"))
      (node (ref "IC25") (pin "9") (pinfunction "A8_9") (pintype "bidirectional"))
    )
    (net (code "186") (name "Net-(IC24A-PB0)") (class "Default")
      (node (ref "IC24") (pin "10") (pinfunction "PB0_10") (pintype "bidirectional"))
      (node (ref "IC26") (pin "2") (pinfunction "A1_2") (pintype "bidirectional"))
    )
    (net (code "187") (name "Net-(IC24A-PB1)") (class "Default")
      (node (ref "IC24") (pin "11") (pinfunction "PB1_11") (pintype "bidirectional"))
      (node (ref "IC26") (pin "3") (pinfunction "A2_3") (pintype "bidirectional"))
    )
    (net (code "188") (name "Net-(IC24A-PB2)") (class "Default")
      (node (ref "IC24") (pin "12") (pinfunction "PB2_12") (pintype "bidirectional"))
      (node (ref "IC26") (pin "4") (pinfunction "A3_4") (pintype "bidirectional"))
    )
    (net (code "189") (name "Net-(IC24A-PB3)") (class "Default")
      (node (ref "IC24") (pin "13") (pinfunction "PB3_13") (pintype "bidirectional"))
      (node (ref "IC26") (pin "5") (pinfunction "A4_5") (pintype "bidirectional"))
    )
    (net (code "190") (name "Net-(IC24A-PB4)") (class "Default")
      (node (ref "IC24") (pin "14") (pinfunction "PB4_14") (pintype "bidirectional"))
      (node (ref "IC26") (pin "6") (pinfunction "A5_6") (pintype "bidirectional"))
    )
    (net (code "191") (name "Net-(IC24A-PB5)") (class "Default")
      (node (ref "IC24") (pin "15") (pinfunction "PB5_15") (pintype "bidirectional"))
      (node (ref "IC26") (pin "7") (pinfunction "A6_7") (pintype "bidirectional"))
    )
    (net (code "192") (name "Net-(IC24A-PB6)") (class "Default")
      (node (ref "IC24") (pin "16") (pinfunction "PB6_16") (pintype "bidirectional"))
      (node (ref "IC26") (pin "8") (pinfunction "A7_8") (pintype "bidirectional"))
    )
    (net (code "193") (name "Net-(IC24A-PB7)") (class "Default")
      (node (ref "IC24") (pin "17") (pinfunction "PB7_17") (pintype "bidirectional"))
      (node (ref "IC26") (pin "9") (pinfunction "A8_9") (pintype "bidirectional"))
    )
    (net (code "194") (name "Net-(IC27A-CV)") (class "Default")
      (node (ref "C7") (pin "1") (pinfunction "1_1") (pintype "passive"))
      (node (ref "IC27") (pin "3") (pinfunction "CV_3") (pintype "input"))
    )
    (net (code "195") (name "Net-(IC27A-DIS)") (class "Default")
      (node (ref "IC27") (pin "1") (pinfunction "DIS_1") (pintype "input"))
      (node (ref "R10") (pin "2") (pinfunction "2_2") (pintype "passive"))
      (node (ref "R9") (pin "1") (pinfunction "1_1") (pintype "passive"))
    )
    (net (code "196") (name "Net-(IC27A-THR)") (class "Default")
      (node (ref "C6") (pin "1") (pinfunction "1_1") (pintype "passive"))
      (node (ref "IC27") (pin "2") (pinfunction "THR_2") (pintype "input"))
      (node (ref "IC27") (pin "6") (pinfunction "TR_6") (pintype "input"))
      (node (ref "R11") (pin "A") (pinfunction "A_A") (pintype "passive"))
    )
    (net (code "197") (name "Net-(IC27B-CV)") (class "Default")
      (node (ref "C5") (pin "1") (pinfunction "1_1") (pintype "passive"))
      (node (ref "IC27") (pin "11") (pinfunction "CV_11") (pintype "input"))
    )
    (net (code "198") (name "Net-(IC27B-DIS)") (class "Default")
      (node (ref "IC27") (pin "13") (pinfunction "DIS_13") (pintype "input"))
      (node (ref "R3") (pin "1") (pinfunction "1_1") (pintype "passive"))
      (node (ref "R4") (pin "2") (pinfunction "2_2") (pintype "passive"))
    )
    (net (code "199") (name "Net-(IC27B-THR)") (class "Default")
      (node (ref "C4") (pin "1") (pinfunction "1_1") (pintype "passive"))
      (node (ref "IC27") (pin "12") (pinfunction "THR_12") (pintype "input"))
      (node (ref "IC27") (pin "8") (pinfunction "TR_8") (pintype "input"))
      (node (ref "R4") (pin "1") (pinfunction "1_1") (pintype "passive"))
    )
    (net (code "200") (name "Net-(LED1-PadA)") (class "Default")
      (node (ref "LED1") (pin "A") (pinfunction "A_A") (pintype "passive"))
      (node (ref "R12") (pin "1") (pinfunction "1_1") (pintype "passive"))
    )
    (net (code "201") (name "Net-(R10-Pad1)") (class "Default")
      (node (ref "R10") (pin "1") (pinfunction "1_1") (pintype "passive"))
      (node (ref "R11") (pin "E") (pinfunction "E_E") (pintype "passive"))
    )
    (net (code "202") (name "Net-(X1-Pad4)") (class "Default")
      (node (ref "X1") (pin "4") (pinfunction "4_4") (pintype "passive"))
      (node (ref "X1") (pin "6") (pinfunction "6_6") (pintype "passive"))
    )
    (net (code "203") (name "Net-(X1-Pad5)") (class "Default")
      (node (ref "X1") (pin "5") (pinfunction "5_5") (pintype "passive"))
      (node (ref "X1") (pin "G1") (pinfunction "G1_G1") (pintype "passive"))
      (node (ref "X1") (pin "G2") (pinfunction "G2_G2") (pintype "passive"))
    )
    (net (code "204") (name "Net-(X1-Pad7)") (class "Default")
      (node (ref "X1") (pin "7") (pinfunction "7_7") (pintype "passive"))
      (node (ref "X1") (pin "8") (pinfunction "8_8") (pintype "passive"))
    )
    (net (code "205") (name "OUT00") (class "Default")
      (node (ref "IC1") (pin "1") (pinfunction "0_1") (pintype "output"))
      (node (ref "IC6") (pin "11") (pinfunction "CLK_11") (pintype "input"))
    )
    (net (code "206") (name "OUT01") (class "Default")
      (node (ref "IC1") (pin "2") (pinfunction "1_2") (pintype "output"))
      (node (ref "IC7") (pin "11") (pinfunction "CLK_11") (pintype "input"))
    )
    (net (code "207") (name "OUT02") (class "Default")
      (node (ref "IC1") (pin "3") (pinfunction "2_3") (pintype "output"))
      (node (ref "IC8") (pin "11") (pinfunction "CLK_11") (pintype "input"))
    )
    (net (code "208") (name "OUT03") (class "Default")
      (node (ref "IC1") (pin "4") (pinfunction "3_4") (pintype "output"))
      (node (ref "IC10") (pin "11") (pinfunction "CLK_11") (pintype "input"))
    )
    (net (code "209") (name "OUT04") (class "Default")
      (node (ref "IC1") (pin "5") (pinfunction "4_5") (pintype "output"))
      (node (ref "IC11") (pin "11") (pinfunction "CLK_11") (pintype "input"))
    )
    (net (code "210") (name "OUT05") (class "Default")
      (node (ref "IC1") (pin "6") (pinfunction "5_6") (pintype "output"))
      (node (ref "IC12") (pin "11") (pinfunction "CLK_11") (pintype "input"))
    )
    (net (code "211") (name "OUT06") (class "Default")
      (node (ref "IC1") (pin "7") (pinfunction "6_7") (pintype "output"))
      (node (ref "IC13") (pin "11") (pinfunction "CLK_11") (pintype "input"))
    )
    (net (code "212") (name "OUT07") (class "Default")
      (node (ref "IC1") (pin "8") (pinfunction "7_8") (pintype "output"))
      (node (ref "IC14") (pin "11") (pinfunction "CLK_11") (pintype "input"))
    )
    (net (code "213") (name "OUT08") (class "Default")
      (node (ref "IC1") (pin "9") (pinfunction "8_9") (pintype "output"))
    )
    (net (code "214") (name "OUT09") (class "Default")
      (node (ref "IC1") (pin "10") (pinfunction "9_10") (pintype "output"))
    )
    (net (code "215") (name "OUT10") (class "Default")
      (node (ref "IC1") (pin "11") (pinfunction "10_11") (pintype "output"))
    )
    (net (code "216") (name "OUT11") (class "Default")
      (node (ref "IC1") (pin "13") (pinfunction "11_13") (pintype "output"))
    )
    (net (code "217") (name "OUT12") (class "Default")
      (node (ref "IC1") (pin "14") (pinfunction "12_14") (pintype "output"))
    )
    (net (code "218") (name "OUT13") (class "Default")
      (node (ref "IC1") (pin "15") (pinfunction "13_15") (pintype "output"))
    )
    (net (code "219") (name "OUT14") (class "Default")
      (node (ref "IC1") (pin "16") (pinfunction "14_16") (pintype "output"))
    )
    (net (code "220") (name "OUT15") (class "Default")
      (node (ref "IC1") (pin "17") (pinfunction "15_17") (pintype "output"))
    )
    (net (code "221") (name "PIA-A0") (class "Default")
      (node (ref "IC10") (pin "3") (pinfunction "1D_3") (pintype "input"))
      (node (ref "IC11") (pin "3") (pinfunction "1D_3") (pintype "input"))
      (node (ref "IC12") (pin "3") (pinfunction "1D_3") (pintype "input"))
      (node (ref "IC13") (pin "3") (pinfunction "1D_3") (pintype "input"))
      (node (ref "IC14") (pin "3") (pinfunction "1D_3") (pintype "input"))
      (node (ref "IC15") (pin "2") (pinfunction "1Q_2") (pintype "tri_state"))
      (node (ref "IC16") (pin "2") (pinfunction "1Q_2") (pintype "tri_state"))
      (node (ref "IC2") (pin "2") (pinfunction "1Q_2") (pintype "tri_state"))
      (node (ref "IC25") (pin "18") (pinfunction "B1_18") (pintype "bidirectional"))
      (node (ref "IC3") (pin "2") (pinfunction "1Q_2") (pintype "tri_state"))
      (node (ref "IC4") (pin "2") (pinfunction "1Q_2") (pintype "tri_state"))
      (node (ref "IC6") (pin "3") (pinfunction "1D_3") (pintype "input"))
      (node (ref "IC7") (pin "3") (pinfunction "1D_3") (pintype "input"))
      (node (ref "IC8") (pin "3") (pinfunction "1D_3") (pintype "input"))
      (node (ref "IC9") (pin "2") (pinfunction "1Q_2") (pintype "tri_state"))
      (node (ref "SV9") (pin "1") (pinfunction "1_1") (pintype "passive"))
    )
    (net (code "222") (name "PIA-A1") (class "Default")
      (node (ref "IC10") (pin "4") (pinfunction "2D_4") (pintype "input"))
      (node (ref "IC11") (pin "4") (pinfunction "2D_4") (pintype "input"))
      (node (ref "IC12") (pin "4") (pinfunction "2D_4") (pintype "input"))
      (node (ref "IC13") (pin "4") (pinfunction "2D_4") (pintype "input"))
      (node (ref "IC14") (pin "4") (pinfunction "2D_4") (pintype "input"))
      (node (ref "IC15") (pin "5") (pinfunction "2Q_5") (pintype "tri_state"))
      (node (ref "IC16") (pin "5") (pinfunction "2Q_5") (pintype "tri_state"))
      (node (ref "IC2") (pin "5") (pinfunction "2Q_5") (pintype "tri_state"))
      (node (ref "IC25") (pin "17") (pinfunction "B2_17") (pintype "bidirectional"))
      (node (ref "IC3") (pin "5") (pinfunction "2Q_5") (pintype "tri_state"))
      (node (ref "IC4") (pin "5") (pinfunction "2Q_5") (pintype "tri_state"))
      (node (ref "IC6") (pin "4") (pinfunction "2D_4") (pintype "input"))
      (node (ref "IC7") (pin "4") (pinfunction "2D_4") (pintype "input"))
      (node (ref "IC8") (pin "4") (pinfunction "2D_4") (pintype "input"))
      (node (ref "IC9") (pin "5") (pinfunction "2Q_5") (pintype "tri_state"))
      (node (ref "SV9") (pin "3") (pinfunction "3_3") (pintype "passive"))
    )
    (net (code "223") (name "PIA-A2") (class "Default")
      (node (ref "IC10") (pin "7") (pinfunction "3D_7") (pintype "input"))
      (node (ref "IC11") (pin "7") (pinfunction "3D_7") (pintype "input"))
      (node (ref "IC12") (pin "7") (pinfunction "3D_7") (pintype "input"))
      (node (ref "IC13") (pin "7") (pinfunction "3D_7") (pintype "input"))
      (node (ref "IC14") (pin "7") (pinfunction "3D_7") (pintype "input"))
      (node (ref "IC15") (pin "6") (pinfunction "3Q_6") (pintype "tri_state"))
      (node (ref "IC16") (pin "6") (pinfunction "3Q_6") (pintype "tri_state"))
      (node (ref "IC2") (pin "6") (pinfunction "3Q_6") (pintype "tri_state"))
      (node (ref "IC25") (pin "16") (pinfunction "B3_16") (pintype "bidirectional"))
      (node (ref "IC3") (pin "6") (pinfunction "3Q_6") (pintype "tri_state"))
      (node (ref "IC4") (pin "6") (pinfunction "3Q_6") (pintype "tri_state"))
      (node (ref "IC6") (pin "7") (pinfunction "3D_7") (pintype "input"))
      (node (ref "IC7") (pin "7") (pinfunction "3D_7") (pintype "input"))
      (node (ref "IC8") (pin "7") (pinfunction "3D_7") (pintype "input"))
      (node (ref "IC9") (pin "6") (pinfunction "3Q_6") (pintype "tri_state"))
      (node (ref "SV9") (pin "5") (pinfunction "5_5") (pintype "passive"))
    )
    (net (code "224") (name "PIA-A3") (class "Default")
      (node (ref "IC10") (pin "8") (pinfunction "4D_8") (pintype "input"))
      (node (ref "IC11") (pin "8") (pinfunction "4D_8") (pintype "input"))
      (node (ref "IC12") (pin "8") (pinfunction "4D_8") (pintype "input"))
      (node (ref "IC13") (pin "8") (pinfunction "4D_8") (pintype "input"))
      (node (ref "IC14") (pin "8") (pinfunction "4D_8") (pintype "input"))
      (node (ref "IC15") (pin "9") (pinfunction "4Q_9") (pintype "tri_state"))
      (node (ref "IC16") (pin "9") (pinfunction "4Q_9") (pintype "tri_state"))
      (node (ref "IC2") (pin "9") (pinfunction "4Q_9") (pintype "tri_state"))
      (node (ref "IC25") (pin "15") (pinfunction "B4_15") (pintype "bidirectional"))
      (node (ref "IC3") (pin "9") (pinfunction "4Q_9") (pintype "tri_state"))
      (node (ref "IC4") (pin "9") (pinfunction "4Q_9") (pintype "tri_state"))
      (node (ref "IC6") (pin "8") (pinfunction "4D_8") (pintype "input"))
      (node (ref "IC7") (pin "8") (pinfunction "4D_8") (pintype "input"))
      (node (ref "IC8") (pin "8") (pinfunction "4D_8") (pintype "input"))
      (node (ref "IC9") (pin "9") (pinfunction "4Q_9") (pintype "tri_state"))
      (node (ref "SV9") (pin "7") (pinfunction "7_7") (pintype "passive"))
    )
    (net (code "225") (name "PIA-A4") (class "Default")
      (node (ref "IC10") (pin "13") (pinfunction "5D_13") (pintype "input"))
      (node (ref "IC11") (pin "13") (pinfunction "5D_13") (pintype "input"))
      (node (ref "IC12") (pin "13") (pinfunction "5D_13") (pintype "input"))
      (node (ref "IC13") (pin "13") (pinfunction "5D_13") (pintype "input"))
      (node (ref "IC14") (pin "13") (pinfunction "5D_13") (pintype "input"))
      (node (ref "IC15") (pin "12") (pinfunction "5Q_12") (pintype "tri_state"))
      (node (ref "IC16") (pin "12") (pinfunction "5Q_12") (pintype "tri_state"))
      (node (ref "IC2") (pin "12") (pinfunction "5Q_12") (pintype "tri_state"))
      (node (ref "IC25") (pin "14") (pinfunction "B5_14") (pintype "bidirectional"))
      (node (ref "IC3") (pin "12") (pinfunction "5Q_12") (pintype "tri_state"))
      (node (ref "IC4") (pin "12") (pinfunction "5Q_12") (pintype "tri_state"))
      (node (ref "IC6") (pin "13") (pinfunction "5D_13") (pintype "input"))
      (node (ref "IC7") (pin "13") (pinfunction "5D_13") (pintype "input"))
      (node (ref "IC8") (pin "13") (pinfunction "5D_13") (pintype "input"))
      (node (ref "IC9") (pin "12") (pinfunction "5Q_12") (pintype "tri_state"))
      (node (ref "SV9") (pin "9") (pinfunction "9_9") (pintype "passive"))
    )
    (net (code "226") (name "PIA-A5") (class "Default")
      (node (ref "IC10") (pin "14") (pinfunction "6D_14") (pintype "input"))
      (node (ref "IC11") (pin "14") (pinfunction "6D_14") (pintype "input"))
      (node (ref "IC12") (pin "14") (pinfunction "6D_14") (pintype "input"))
      (node (ref "IC13") (pin "14") (pinfunction "6D_14") (pintype "input"))
      (node (ref "IC14") (pin "14") (pinfunction "6D_14") (pintype "input"))
      (node (ref "IC15") (pin "15") (pinfunction "6Q_15") (pintype "tri_state"))
      (node (ref "IC16") (pin "15") (pinfunction "6Q_15") (pintype "tri_state"))
      (node (ref "IC2") (pin "15") (pinfunction "6Q_15") (pintype "tri_state"))
      (node (ref "IC25") (pin "13") (pinfunction "B6_13") (pintype "bidirectional"))
      (node (ref "IC3") (pin "15") (pinfunction "6Q_15") (pintype "tri_state"))
      (node (ref "IC4") (pin "15") (pinfunction "6Q_15") (pintype "tri_state"))
      (node (ref "IC6") (pin "14") (pinfunction "6D_14") (pintype "input"))
      (node (ref "IC7") (pin "14") (pinfunction "6D_14") (pintype "input"))
      (node (ref "IC8") (pin "14") (pinfunction "6D_14") (pintype "input"))
      (node (ref "IC9") (pin "15") (pinfunction "6Q_15") (pintype "tri_state"))
      (node (ref "SV9") (pin "11") (pinfunction "11_11") (pintype "passive"))
    )
    (net (code "227") (name "PIA-A6") (class "Default")
      (node (ref "IC10") (pin "17") (pinfunction "7D_17") (pintype "input"))
      (node (ref "IC11") (pin "17") (pinfunction "7D_17") (pintype "input"))
      (node (ref "IC12") (pin "17") (pinfunction "7D_17") (pintype "input"))
      (node (ref "IC13") (pin "17") (pinfunction "7D_17") (pintype "input"))
      (node (ref "IC14") (pin "17") (pinfunction "7D_17") (pintype "input"))
      (node (ref "IC15") (pin "16") (pinfunction "7Q_16") (pintype "tri_state"))
      (node (ref "IC16") (pin "16") (pinfunction "7Q_16") (pintype "tri_state"))
      (node (ref "IC2") (pin "16") (pinfunction "7Q_16") (pintype "tri_state"))
      (node (ref "IC25") (pin "12") (pinfunction "B7_12") (pintype "bidirectional"))
      (node (ref "IC3") (pin "16") (pinfunction "7Q_16") (pintype "tri_state"))
      (node (ref "IC4") (pin "16") (pinfunction "7Q_16") (pintype "tri_state"))
      (node (ref "IC6") (pin "17") (pinfunction "7D_17") (pintype "input"))
      (node (ref "IC7") (pin "17") (pinfunction "7D_17") (pintype "input"))
      (node (ref "IC8") (pin "17") (pinfunction "7D_17") (pintype "input"))
      (node (ref "IC9") (pin "16") (pinfunction "7Q_16") (pintype "tri_state"))
      (node (ref "SV9") (pin "13") (pinfunction "13_13") (pintype "passive"))
    )
    (net (code "228") (name "PIA-A7") (class "Default")
      (node (ref "IC10") (pin "18") (pinfunction "8D_18") (pintype "input"))
      (node (ref "IC11") (pin "18") (pinfunction "8D_18") (pintype "input"))
      (node (ref "IC12") (pin "18") (pinfunction "8D_18") (pintype "input"))
      (node (ref "IC13") (pin "18") (pinfunction "8D_18") (pintype "input"))
      (node (ref "IC14") (pin "18") (pinfunction "8D_18") (pintype "input"))
      (node (ref "IC15") (pin "19") (pinfunction "8Q_19") (pintype "tri_state"))
      (node (ref "IC16") (pin "19") (pinfunction "8Q_19") (pintype "tri_state"))
      (node (ref "IC2") (pin "19") (pinfunction "8Q_19") (pintype "tri_state"))
      (node (ref "IC25") (pin "11") (pinfunction "B8_11") (pintype "bidirectional"))
      (node (ref "IC3") (pin "19") (pinfunction "8Q_19") (pintype "tri_state"))
      (node (ref "IC4") (pin "19") (pinfunction "8Q_19") (pintype "tri_state"))
      (node (ref "IC6") (pin "18") (pinfunction "8D_18") (pintype "input"))
      (node (ref "IC7") (pin "18") (pinfunction "8D_18") (pintype "input"))
      (node (ref "IC8") (pin "18") (pinfunction "8D_18") (pintype "input"))
      (node (ref "IC9") (pin "19") (pinfunction "8Q_19") (pintype "tri_state"))
      (node (ref "SV9") (pin "15") (pinfunction "15_15") (pintype "passive"))
    )
    (net (code "229") (name "PIA-B0") (class "Default")
      (node (ref "IC1") (pin "23") (pinfunction "A_23") (pintype "input"))
      (node (ref "IC26") (pin "18") (pinfunction "B1_18") (pintype "bidirectional"))
      (node (ref "IC5") (pin "23") (pinfunction "A_23") (pintype "input"))
      (node (ref "SV9") (pin "2") (pinfunction "2_2") (pintype "passive"))
    )
    (net (code "230") (name "PIA-B1") (class "Default")
      (node (ref "IC1") (pin "22") (pinfunction "B_22") (pintype "input"))
      (node (ref "IC26") (pin "17") (pinfunction "B2_17") (pintype "bidirectional"))
      (node (ref "IC5") (pin "22") (pinfunction "B_22") (pintype "input"))
      (node (ref "SV9") (pin "4") (pinfunction "4_4") (pintype "passive"))
    )
    (net (code "231") (name "PIA-B2") (class "Default")
      (node (ref "IC1") (pin "21") (pinfunction "C_21") (pintype "input"))
      (node (ref "IC26") (pin "16") (pinfunction "B3_16") (pintype "bidirectional"))
      (node (ref "IC5") (pin "21") (pinfunction "C_21") (pintype "input"))
      (node (ref "SV9") (pin "6") (pinfunction "6_6") (pintype "passive"))
    )
    (net (code "232") (name "PIA-B3") (class "Default")
      (node (ref "IC1") (pin "20") (pinfunction "D_20") (pintype "input"))
      (node (ref "IC26") (pin "15") (pinfunction "B4_15") (pintype "bidirectional"))
      (node (ref "IC5") (pin "20") (pinfunction "D_20") (pintype "input"))
      (node (ref "SV9") (pin "8") (pinfunction "8_8") (pintype "passive"))
    )
    (net (code "233") (name "PIA-B4") (class "Default")
      (node (ref "IC26") (pin "14") (pinfunction "B5_14") (pintype "bidirectional"))
      (node (ref "IC5") (pin "18") (pinfunction "G1_18") (pintype "input"))
      (node (ref "SV9") (pin "10") (pinfunction "10_10") (pintype "passive"))
    )
    (net (code "234") (name "PIA-B5") (class "Default")
      (node (ref "IC1") (pin "18") (pinfunction "G1_18") (pintype "input"))
      (node (ref "IC26") (pin "13") (pinfunction "B6_13") (pintype "bidirectional"))
      (node (ref "SV9") (pin "12") (pinfunction "12_12") (pintype "passive"))
    )
    (net (code "235") (name "PIA-B6") (class "Default")
      (node (ref "IC26") (pin "12") (pinfunction "B7_12") (pintype "bidirectional"))
      (node (ref "SV9") (pin "14") (pinfunction "14_14") (pintype "passive"))
    )
    (net (code "236") (name "PIA-B7") (class "Default")
      (node (ref "IC26") (pin "11") (pinfunction "B8_11") (pintype "bidirectional"))
      (node (ref "SV9") (pin "16") (pinfunction "16_16") (pintype "passive"))
    )
    (net (code "237") (name "RX") (class "Default")
      (node (ref "IC20") (pin "12") (pinfunction "R1OUT_12") (pintype "output"))
      (node (ref "IC21") (pin "2") (pinfunction "RXDATA_2") (pintype "input"))
    )
    (net (code "238") (name "RXD") (class "Default")
      (node (ref "IC20") (pin "13") (pinfunction "R1IN_13") (pintype "input"))
      (node (ref "X1") (pin "2") (pinfunction "2_2") (pintype "passive"))
    )
    (net (code "239") (name "R{slash}~{W}") (class "Default")
      (node (ref "IC17") (pin "34") (pinfunction "R/~{W}_34") (pintype "output"))
      (node (ref "IC21") (pin "13") (pinfunction "R/~{W}_13") (pintype "input"))
      (node (ref "IC22") (pin "27") (pinfunction "~{PGM}_27") (pintype "input"))
      (node (ref "IC24") (pin "21") (pinfunction "R/~{W}_21") (pintype "input"))
    )
    (net (code "240") (name "TX") (class "Default")
      (node (ref "IC20") (pin "11") (pinfunction "T1IN_11") (pintype "input"))
      (node (ref "IC21") (pin "6") (pinfunction "TXDATA_6") (pintype "output"))
    )
    (net (code "241") (name "TXD") (class "Default")
      (node (ref "IC20") (pin "14") (pinfunction "T1OUT_14") (pintype "output"))
      (node (ref "X1") (pin "3") (pinfunction "3_3") (pintype "passive"))
    )
    (net (code "242") (name "VCC") (class "Default")
      (node (ref "C10") (pin "1") (pinfunction "1_1") (pintype "passive"))
      (node (ref "IC15") (pin "11") (pinfunction "ENC_11") (pintype "input"))
      (node (ref "IC16") (pin "11") (pinfunction "ENC_11") (pintype "input"))
      (node (ref "IC17") (pin "35") (pinfunction "VCCSTB_35") (pintype "input"))
      (node (ref "IC17") (pin "36") (pinfunction "RE_36") (pintype "input"))
      (node (ref "IC17") (pin "8") (pinfunction "VCC_8") (pintype "power_in"))
      (node (ref "IC2") (pin "11") (pinfunction "ENC_11") (pintype "input"))
      (node (ref "IC21") (pin "10") (pinfunction "CS1_10") (pintype "input"))
      (node (ref "IC21") (pin "12") (pinfunction "VCC_12") (pintype "power_in"))
      (node (ref "IC21") (pin "8") (pinfunction "CS0_8") (pintype "input"))
      (node (ref "IC22") (pin "1") (pinfunction "VPP_1") (pintype "input"))
      (node (ref "IC23") (pin "1") (pinfunction "VPP_1") (pintype "input"))
      (node (ref "IC23") (pin "27") (pinfunction "~{PGM}_27") (pintype "input"))
      (node (ref "IC24") (pin "20") (pinfunction "VCC_20") (pintype "power_in"))
      (node (ref "IC24") (pin "22") (pinfunction "CS0_22") (pintype "input"))
      (node (ref "IC24") (pin "24") (pinfunction "CS1_24") (pintype "input"))
      (node (ref "IC27") (pin "10") (pinfunction "R_10") (pintype "input"))
      (node (ref "IC27") (pin "14") (pinfunction "V+_14") (pintype "power_in"))
      (node (ref "IC27") (pin "4") (pinfunction "R_4") (pintype "input"))
      (node (ref "IC28") (pin "6") (pinfunction "G1_6") (pintype "input"))
      (node (ref "IC29") (pin "1") (pinfunction "VPP_1") (pintype "input"))
      (node (ref "IC29") (pin "27") (pinfunction "~{PGM}_27") (pintype "input"))
      (node (ref "IC3") (pin "11") (pinfunction "ENC_11") (pintype "input"))
      (node (ref "IC4") (pin "11") (pinfunction "ENC_11") (pintype "input"))
      (node (ref "IC9") (pin "11") (pinfunction "ENC_11") (pintype "input"))
      (node (ref "JP2") (pin "2") (pinfunction "2_2") (pintype "passive"))
      (node (ref "R1") (pin "2") (pinfunction "2_2") (pintype "passive"))
      (node (ref "R12") (pin "2") (pinfunction "2_2") (pintype "passive"))
      (node (ref "R14") (pin "2") (pinfunction "2_2") (pintype "passive"))
      (node (ref "R2") (pin "2") (pinfunction "2_2") (pintype "passive"))
      (node (ref "R3") (pin "2") (pinfunction "2_2") (pintype "passive"))
      (node (ref "R5") (pin "2") (pinfunction "2_2") (pintype "passive"))
      (node (ref "R6") (pin "2") (pinfunction "2_2") (pintype "passive"))
      (node (ref "R7") (pin "2") (pinfunction "2_2") (pintype "passive"))
      (node (ref "R8") (pin "2") (pinfunction "2_2") (pintype "passive"))
      (node (ref "R9") (pin "2") (pinfunction "2_2") (pintype "passive"))
      (node (ref "SV9") (pin "17") (pinfunction "17_17") (pintype "passive"))
      (node (ref "SV9") (pin "19") (pinfunction "19_19") (pintype "passive"))
    )
    (net (code "243") (name "VMA") (class "Default")
      (node (ref "IC17") (pin "5") (pinfunction "VMA_5") (pintype "output"))
      (node (ref "IC18") (pin "9") (pinfunction "I0_9") (pintype "input"))
    )
    (net (code "244") (name "unconnected-(IC17A-BA-Pad7)") (class "Default")
      (node (ref "IC17") (pin "7") (pinfunction "BA_7") (pintype "output"))
    )
    (net (code "245") (name "unconnected-(IC19A-Y0-Pad15)") (class "Default")
      (node (ref "IC19") (pin "15") (pinfunction "Y0_15") (pintype "output"))
    )
    (net (code "246") (name "unconnected-(IC19A-Y1-Pad14)") (class "Default")
      (node (ref "IC19") (pin "14") (pinfunction "Y1_14") (pintype "output"))
    )
    (net (code "247") (name "unconnected-(IC19A-Y2-Pad13)") (class "Default")
      (node (ref "IC19") (pin "13") (pinfunction "Y2_13") (pintype "output"))
    )
    (net (code "248") (name "unconnected-(IC19A-Y3-Pad12)") (class "Default")
      (node (ref "IC19") (pin "12") (pinfunction "Y3_12") (pintype "output"))
    )
    (net (code "249") (name "unconnected-(IC19A-Y4-Pad11)") (class "Default")
      (node (ref "IC19") (pin "11") (pinfunction "Y4_11") (pintype "output"))
    )
    (net (code "250") (name "unconnected-(IC19A-Y5-Pad10)") (class "Default")
      (node (ref "IC19") (pin "10") (pinfunction "Y5_10") (pintype "output"))
    )
    (net (code "251") (name "unconnected-(IC20A-R2OUT-Pad9)") (class "Default")
      (node (ref "IC20") (pin "9") (pinfunction "R2OUT_9") (pintype "output"))
    )
    (net (code "252") (name "unconnected-(IC28A-Y1-Pad14)") (class "Default")
      (node (ref "IC28") (pin "14") (pinfunction "Y1_14") (pintype "output"))
    )
    (net (code "253") (name "unconnected-(IC28A-Y2-Pad13)") (class "Default")
      (node (ref "IC28") (pin "13") (pinfunction "Y2_13") (pintype "output"))
    )
    (net (code "254") (name "unconnected-(IC28A-Y3-Pad12)") (class "Default")
      (node (ref "IC28") (pin "12") (pinfunction "Y3_12") (pintype "output"))
    )
    (net (code "255") (name "unconnected-(IC28A-Y4-Pad11)") (class "Default")
      (node (ref "IC28") (pin "11") (pinfunction "Y4_11") (pintype "output"))
    )
    (net (code "256") (name "unconnected-(R11-PadS)") (class "Default")
      (node (ref "R11") (pin "S") (pinfunction "S_S") (pintype "passive"))
    )
    (net (code "257") (name "unconnected-(X1-Pad1)") (class "Default")
      (node (ref "X1") (pin "1") (pinfunction "1_1") (pintype "passive"))
    )
    (net (code "258") (name "unconnected-(X1-Pad9)") (class "Default")
      (node (ref "X1") (pin "9") (pinfunction "9_9") (pintype "passive"))
    )
    (net (code "259") (name "~{AB}") (class "Default")
      (node (ref "IC22") (pin "20") (pinfunction "~{CE}_20") (pintype "input"))
      (node (ref "IC22") (pin "22") (pinfunction "~{OE}_22") (pintype "input"))
      (node (ref "IC28") (pin "10") (pinfunction "Y5_10") (pintype "output"))
    )
    (net (code "260") (name "~{CD}") (class "Default")
      (node (ref "IC28") (pin "9") (pinfunction "Y6_9") (pintype "output"))
      (node (ref "IC29") (pin "20") (pinfunction "~{CE}_20") (pintype "input"))
      (node (ref "IC29") (pin "22") (pinfunction "~{OE}_22") (pintype "input"))
    )
    (net (code "261") (name "~{EF}") (class "Default")
      (node (ref "IC23") (pin "20") (pinfunction "~{CE}_20") (pintype "input"))
      (node (ref "IC23") (pin "22") (pinfunction "~{OE}_22") (pintype "input"))
      (node (ref "IC28") (pin "7") (pinfunction "Y7_7") (pintype "output"))
    )
    (net (code "262") (name "~{HLT}") (class "Default")
      (node (ref "IC17") (pin "2") (pinfunction "HALT_2") (pintype "input"))
      (node (ref "R5") (pin "1") (pinfunction "1_1") (pintype "passive"))
    )
    (net (code "263") (name "~{IO-E}") (class "Default")
      (node (ref "IC19") (pin "9") (pinfunction "Y6_9") (pintype "output"))
      (node (ref "IC24") (pin "23") (pinfunction "CS2_23") (pintype "input"))
    )
    (net (code "264") (name "~{IO-F}") (class "Default")
      (node (ref "IC19") (pin "7") (pinfunction "Y7_7") (pintype "output"))
      (node (ref "IC21") (pin "9") (pinfunction "CS2_9") (pintype "input"))
    )
    (net (code "265") (name "~{IRQ}") (class "Default")
      (node (ref "IC17") (pin "4") (pinfunction "IRQ_4") (pintype "input"))
      (node (ref "IC24") (pin "37") (pinfunction "IRQB_37") (pintype "open_collector"))
      (node (ref "IC24") (pin "38") (pinfunction "IRQA_38") (pintype "open_collector"))
      (node (ref "R7") (pin "1") (pinfunction "1_1") (pintype "passive"))
    )
    (net (code "266") (name "~{NMI}") (class "Default")
      (node (ref "IC17") (pin "6") (pinfunction "NMI_6") (pintype "input"))
      (node (ref "IC21") (pin "7") (pinfunction "IRQ_7") (pintype "output"))
      (node (ref "R6") (pin "1") (pinfunction "1_1") (pintype "passive"))
    )
    (net (code "267") (name "~{RST}") (class "Default")
      (node (ref "IC17") (pin "40") (pinfunction "RESET_40") (pintype "input"))
      (node (ref "IC18") (pin "6") (pinfunction "O_6") (pintype "output"))
      (node (ref "IC24") (pin "34") (pinfunction "RESET_34") (pintype "input"))
    )
  )
)
